# Easy_RFPA_RevB_S2.net
KiCad netlist of a schematic drawn in EAGLE
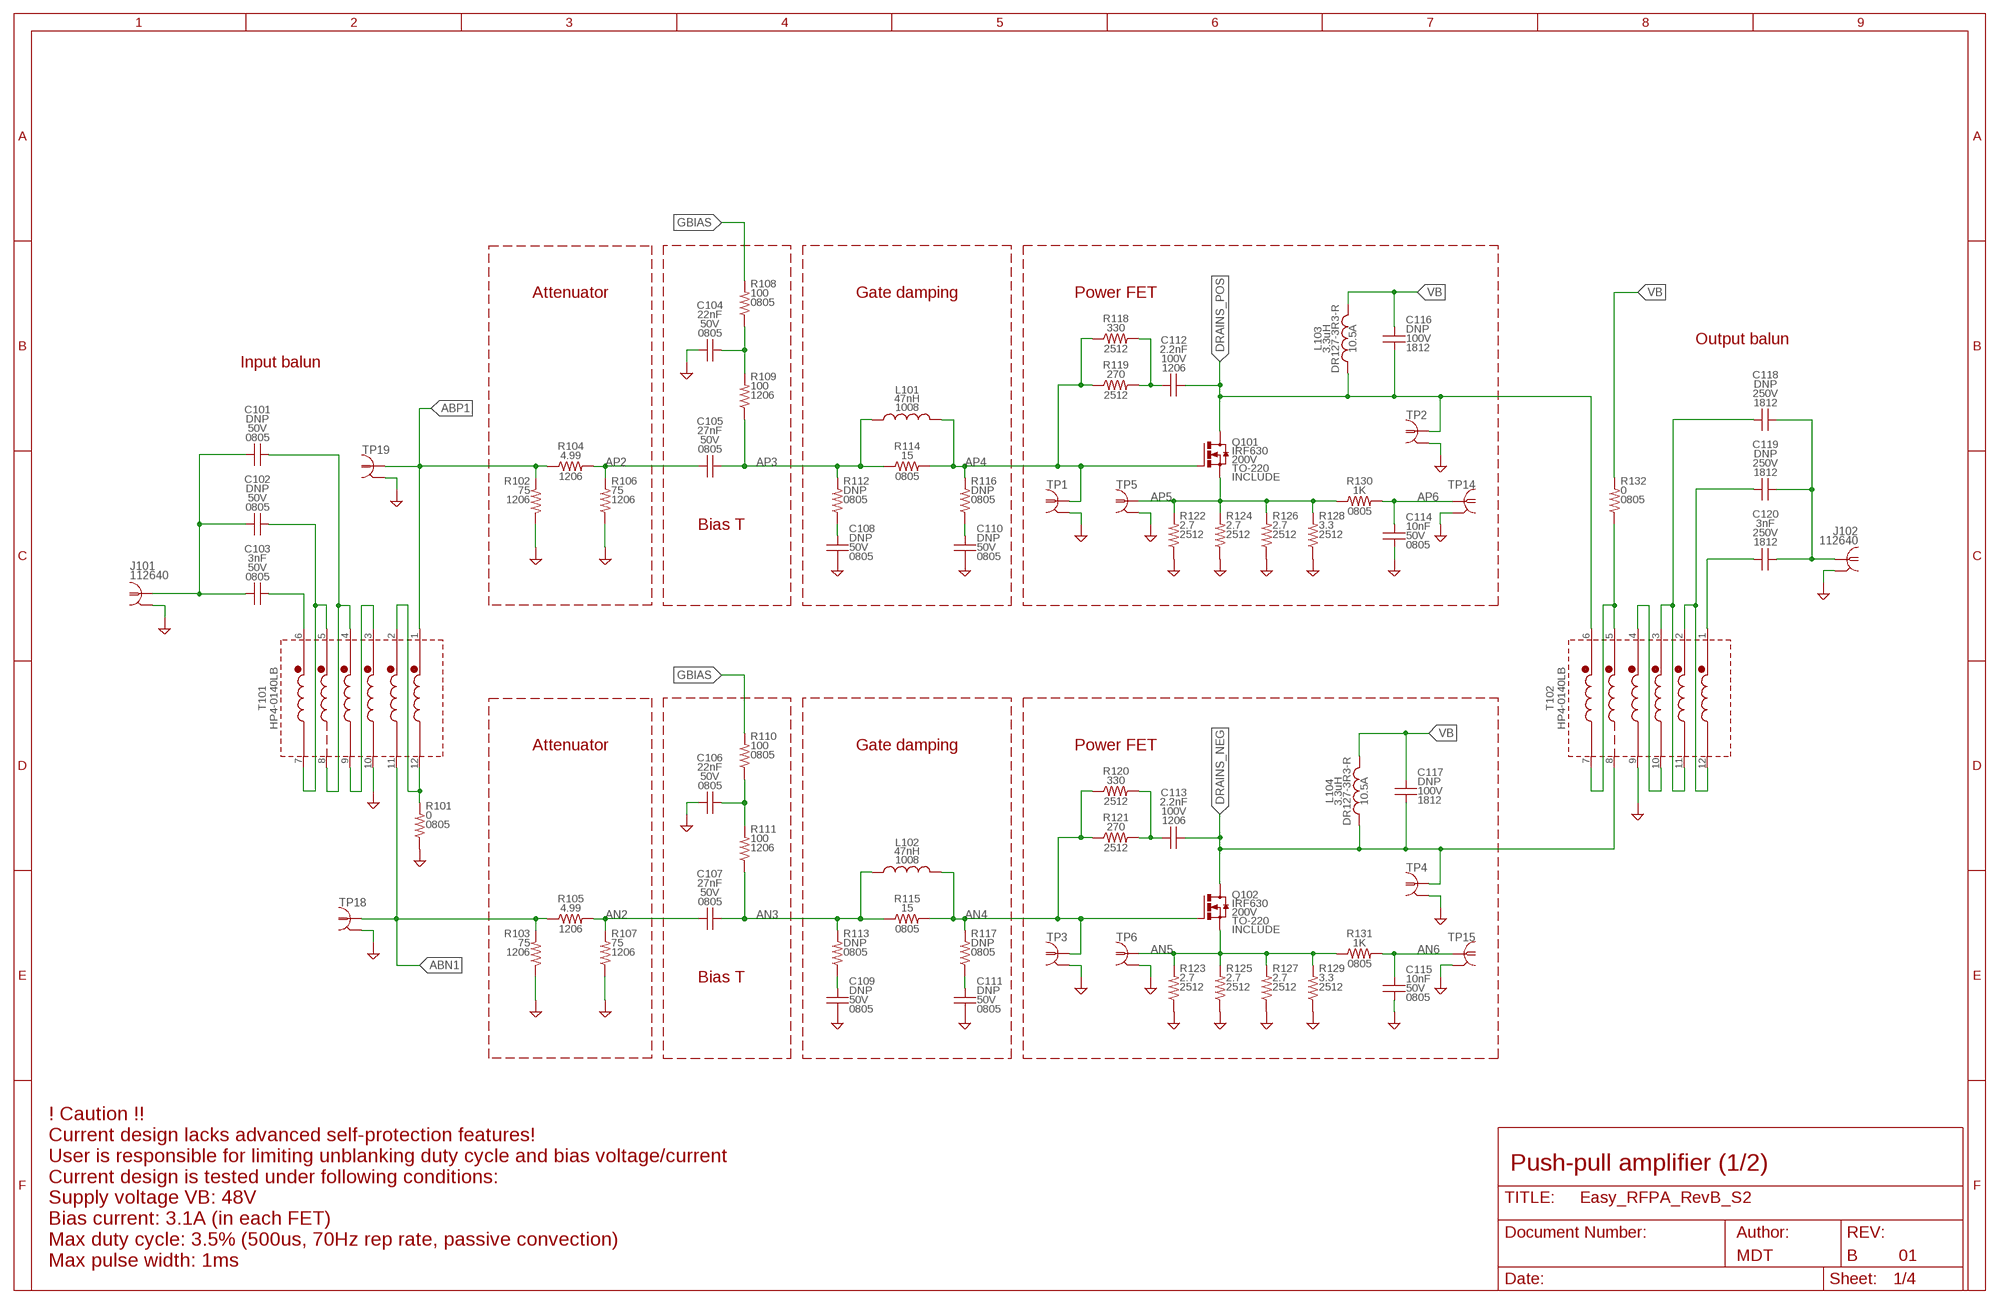
[diagram p0: schematic, sheet 1]
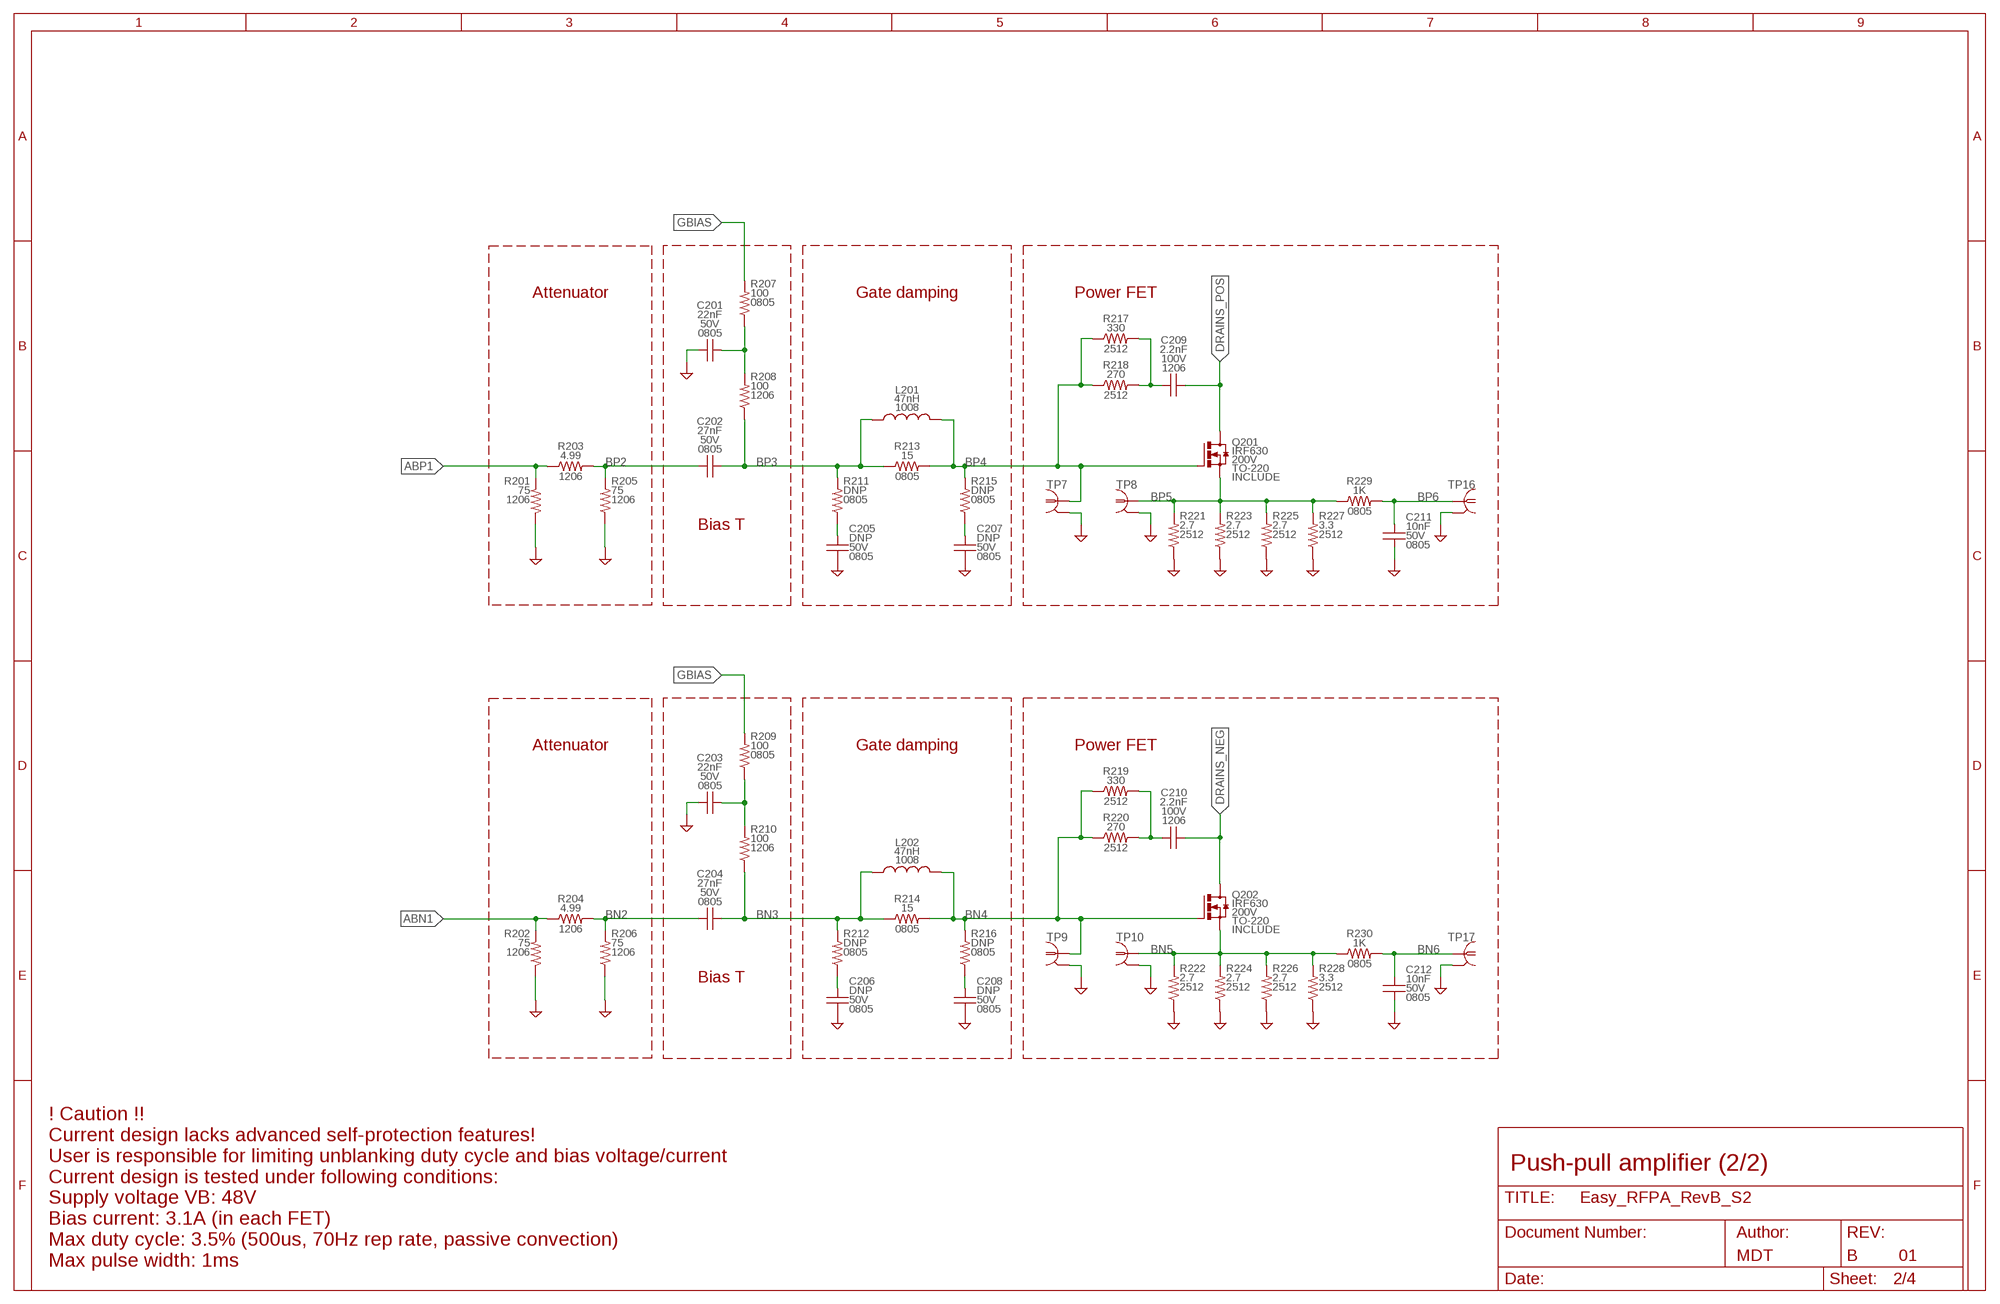
[diagram p1: schematic, sheet 2]
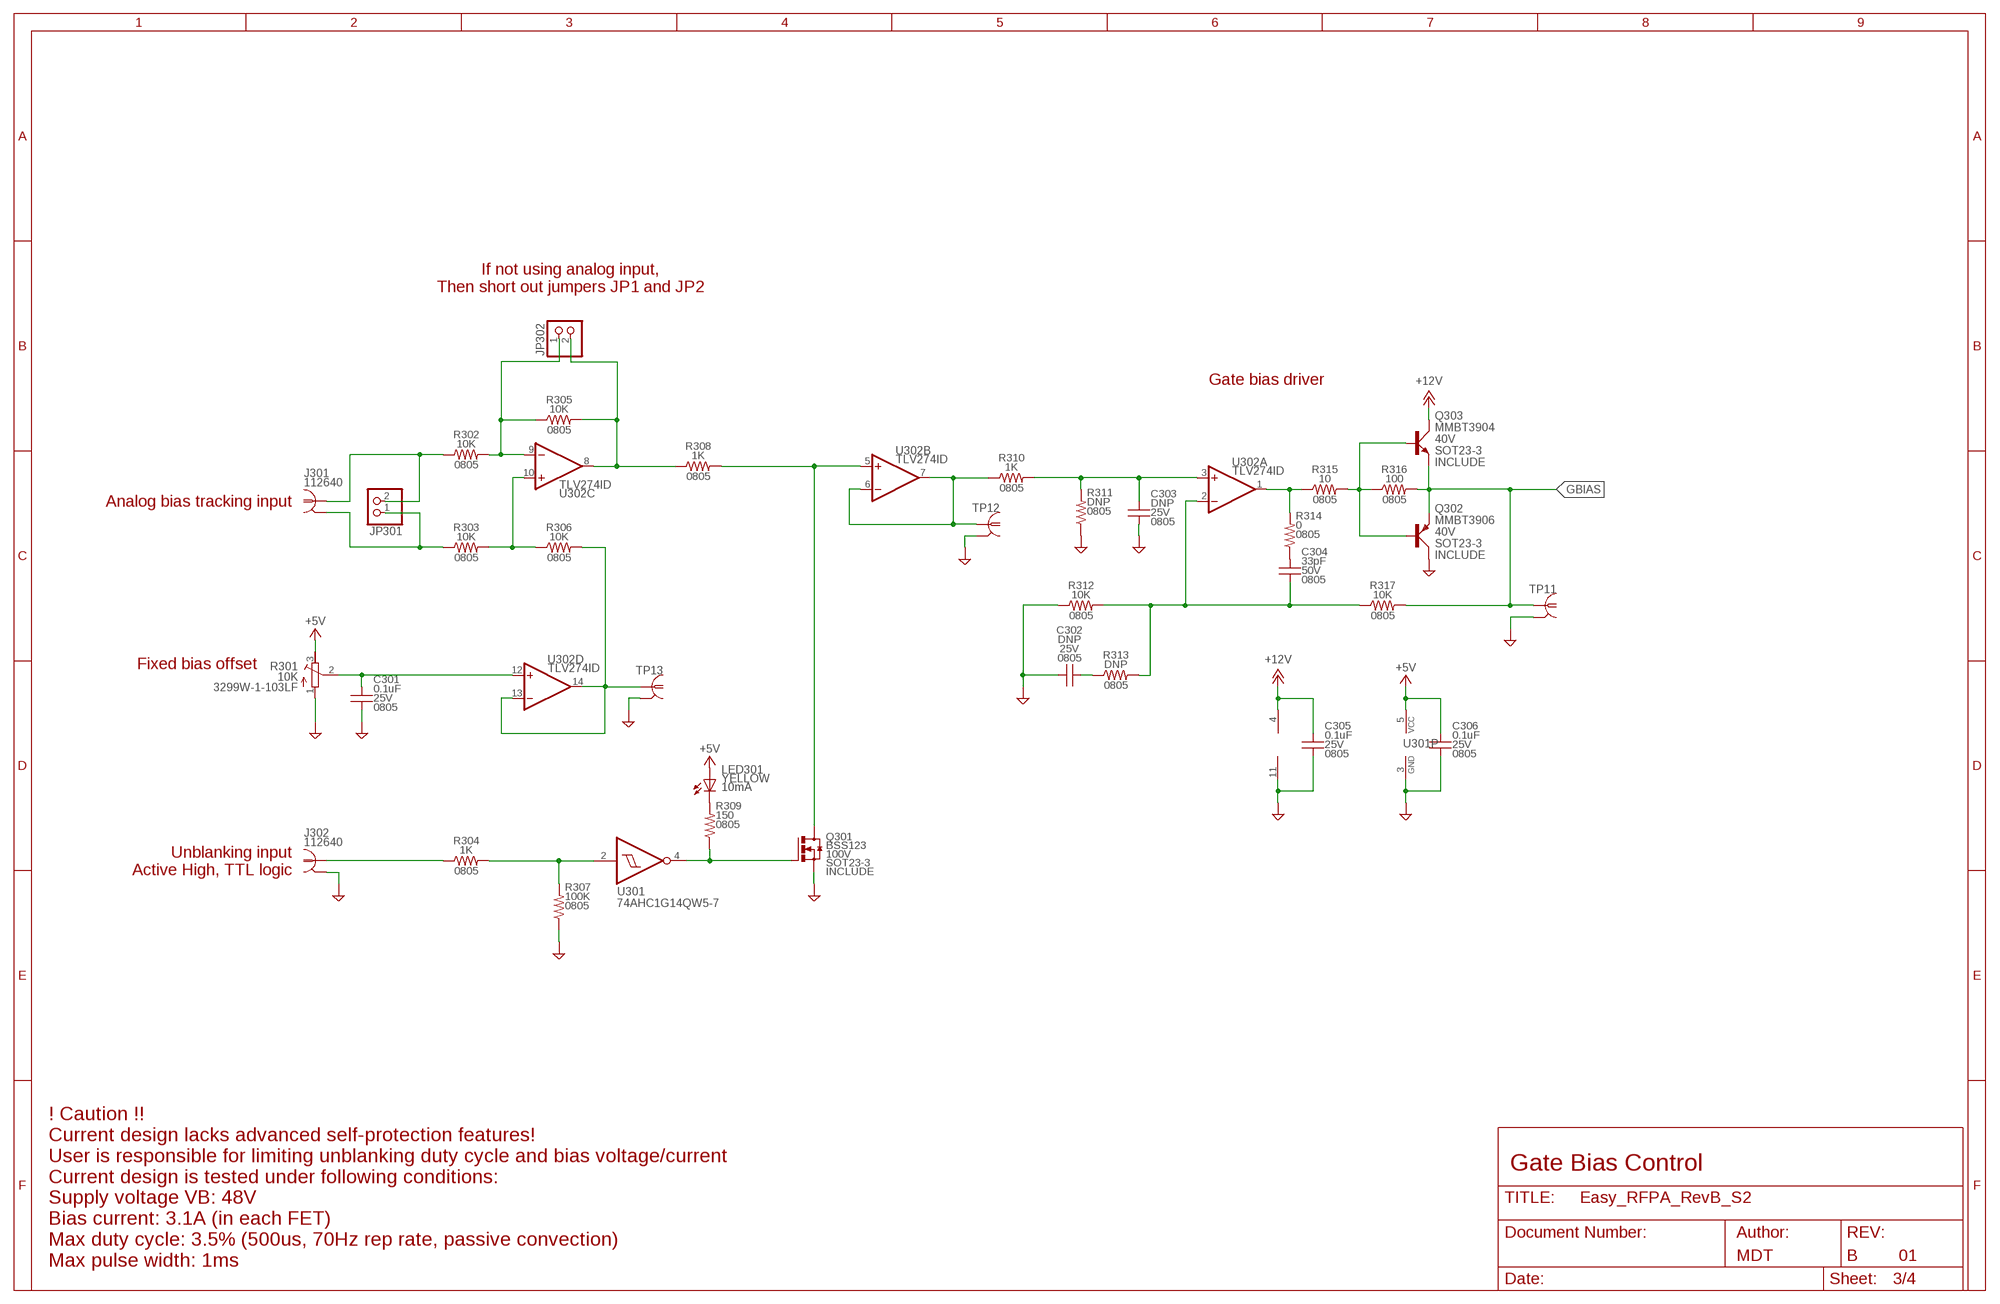
[diagram p2: schematic, sheet 3]
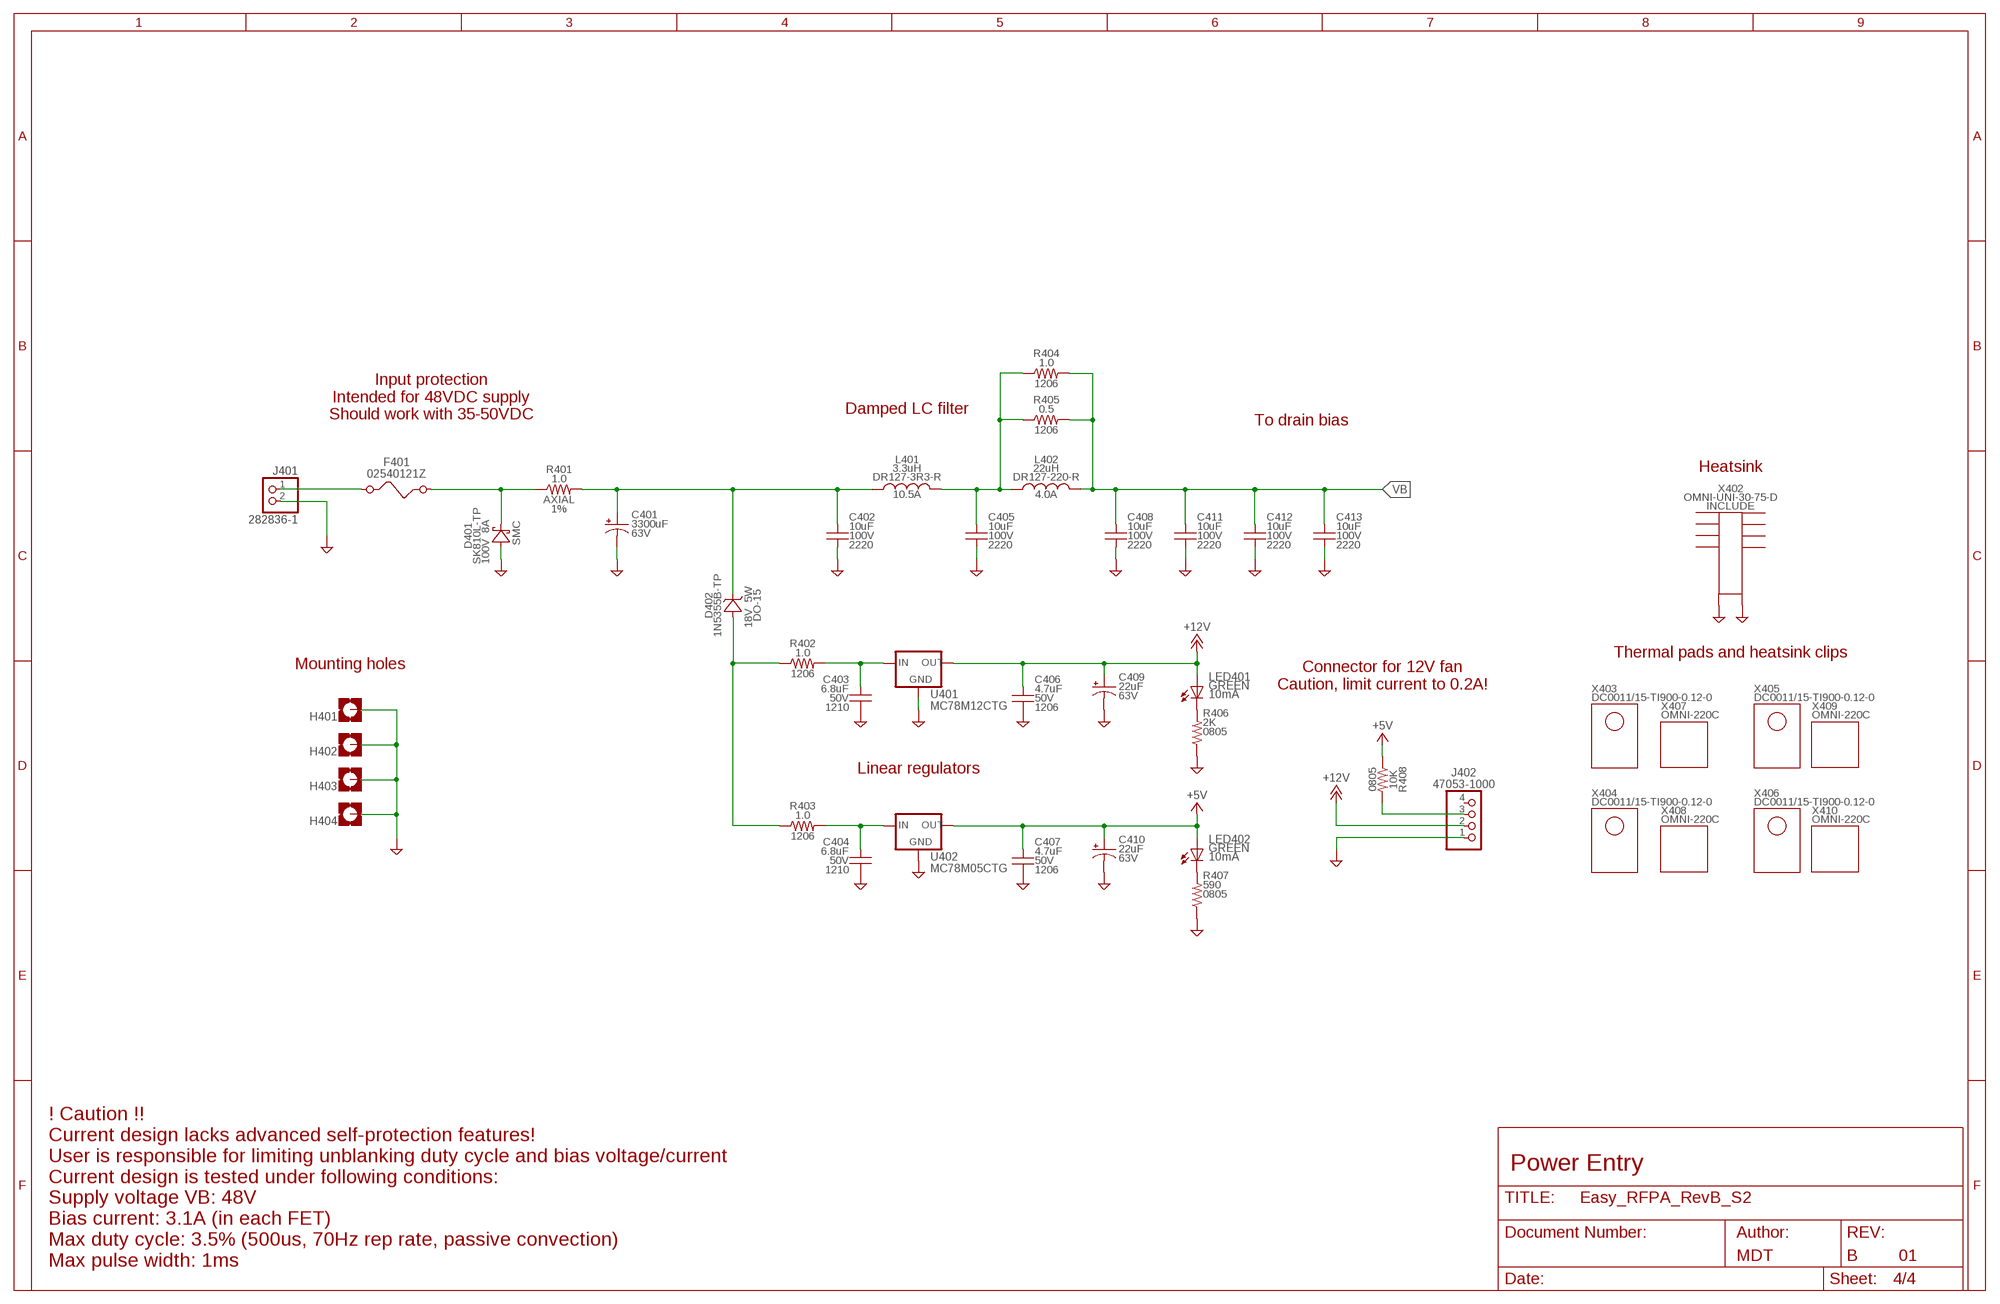
[diagram p3: schematic, sheet 4]

(export (version "E")
  (design (tool "Eeschema 10.0.6"))
  (components
    (comp (ref "C101")
      (value "DNP")
      (footprint "eagle-import:0805_IPC-7351B")
      (fields (field (name "PACKAGE") "0805") (field (name "BOM") "EXCLUDE") (field (name "VOLTAGE") "50V"))
      (libsource (lib "eagle-import") (part "C0805_IPCGEN"))
    )
    (comp (ref "C102")
      (value "DNP")
      (footprint "eagle-import:0805_IPC-7351B")
      (fields (field (name "PACKAGE") "0805") (field (name "BOM") "EXCLUDE") (field (name "VOLTAGE") "50V"))
      (libsource (lib "eagle-import") (part "C0805_IPCGEN"))
    )
    (comp (ref "C103")
      (value "3nF")
      (footprint "eagle-import:0805_IPC-7351B")
      (fields (field (name "PACKAGE") "0805") (field (name "VOLTAGE") "50V"))
      (libsource (lib "eagle-import") (part "C0805_IPCGEN"))
    )
    (comp (ref "C104")
      (value "22nF")
      (footprint "eagle-import:0805_IPC-7351B")
      (fields (field (name "BOM") "INCLUDE") (field (name "PACKAGE") "0805") (field (name "VOLTAGE") "50V"))
      (libsource (lib "eagle-import") (part "C0805_IPCGEN"))
    )
    (comp (ref "C105")
      (value "27nF")
      (footprint "eagle-import:0805_IPC-7351B")
      (fields (field (name "PACKAGE") "0805") (field (name "VOLTAGE") "50V"))
      (libsource (lib "eagle-import") (part "C0805_IPCGEN"))
    )
    (comp (ref "C106")
      (value "22nF")
      (footprint "eagle-import:0805_IPC-7351B")
      (fields (field (name "PACKAGE") "0805") (field (name "VOLTAGE") "50V"))
      (libsource (lib "eagle-import") (part "C0805_IPCGEN"))
    )
    (comp (ref "C107")
      (value "27nF")
      (footprint "eagle-import:0805_IPC-7351B")
      (fields (field (name "PACKAGE") "0805") (field (name "VOLTAGE") "50V"))
      (libsource (lib "eagle-import") (part "C0805_IPCGEN"))
    )
    (comp (ref "C108")
      (value "DNP")
      (footprint "eagle-import:0805_IPC-7351B")
      (fields (field (name "BOM") "EXCLUDE") (field (name "VOLTAGE") "50V"))
      (libsource (lib "eagle-import") (part "C0805_IPCGEN"))
    )
    (comp (ref "C109")
      (value "DNP")
      (footprint "eagle-import:0805_IPC-7351B")
      (fields (field (name "BOM") "EXCLUDE") (field (name "VOLTAGE") "50V"))
      (libsource (lib "eagle-import") (part "C0805_IPCGEN"))
    )
    (comp (ref "C110")
      (value "DNP")
      (footprint "eagle-import:0805_IPC-7351B")
      (fields (field (name "BOM") "EXCLUDE") (field (name "VOLTAGE") "50V"))
      (libsource (lib "eagle-import") (part "C0805_IPCGEN"))
    )
    (comp (ref "C111")
      (value "DNP")
      (footprint "eagle-import:0805_IPC-7351B")
      (fields (field (name "BOM") "EXCLUDE") (field (name "VOLTAGE") "50V"))
      (libsource (lib "eagle-import") (part "C0805_IPCGEN"))
    )
    (comp (ref "C112")
      (value "2.2nF")
      (footprint "eagle-import:C1206")
      (fields (field (name "PACKAGE") "1206") (field (name "VOLTAGE") "100V"))
      (libsource (lib "eagle-import") (part "CC1206GEN"))
    )
    (comp (ref "C113")
      (value "2.2nF")
      (footprint "eagle-import:C1206")
      (fields (field (name "PACKAGE") "1206") (field (name "VOLTAGE") "100V"))
      (libsource (lib "eagle-import") (part "CC1206GEN"))
    )
    (comp (ref "C114")
      (value "10nF")
      (footprint "eagle-import:0805_IPC-7351B")
      (fields (field (name "VOLTAGE") "50V"))
      (libsource (lib "eagle-import") (part "C0805_IPCGEN"))
    )
    (comp (ref "C115")
      (value "10nF")
      (footprint "eagle-import:0805_IPC-7351B")
      (fields (field (name "VOLTAGE") "50V"))
      (libsource (lib "eagle-import") (part "C0805_IPCGEN"))
    )
    (comp (ref "C116")
      (value "DNP")
      (footprint "eagle-import:C1812")
      (fields (field (name "BOM") "EXCLUDE") (field (name "VOLTAGE") "100V"))
      (libsource (lib "eagle-import") (part "CC1812GEN"))
    )
    (comp (ref "C117")
      (value "DNP")
      (footprint "eagle-import:C1812")
      (fields (field (name "BOM") "EXCLUDE") (field (name "VOLTAGE") "100V"))
      (libsource (lib "eagle-import") (part "CC1812GEN"))
    )
    (comp (ref "C118")
      (value "DNP")
      (footprint "eagle-import:C1812")
      (fields (field (name "PACKAGE") "1812") (field (name "BOM") "EXCLUDE") (field (name "VOLTAGE") "250V"))
      (libsource (lib "eagle-import") (part "CC1812GEN"))
    )
    (comp (ref "C119")
      (value "DNP")
      (footprint "eagle-import:C1812")
      (fields (field (name "PACKAGE") "1812") (field (name "BOM") "EXCLUDE") (field (name "VOLTAGE") "250V"))
      (libsource (lib "eagle-import") (part "CC1812GEN"))
    )
    (comp (ref "C120")
      (value "3nF")
      (footprint "eagle-import:C1812")
      (fields (field (name "PACKAGE") "1812") (field (name "VOLTAGE") "250V"))
      (libsource (lib "eagle-import") (part "CC1812GEN"))
    )
    (comp (ref "J101")
      (value "COAX112640BNC_EDGE")
      (footprint "eagle-import:BNC_EDGE")
      (fields (field (name "PARTNO") "112640"))
      (libsource (lib "eagle-import") (part "COAXBNC_EDGE112640"))
    )
    (comp (ref "J102")
      (value "COAX112640BNC_EDGE")
      (footprint "eagle-import:BNC_EDGE")
      (fields (field (name "PARTNO") "112640"))
      (libsource (lib "eagle-import") (part "COAXBNC_EDGE112640"))
    )
    (comp (ref "L101")
      (value "47nH")
      (footprint "eagle-import:L1008")
      (fields (field (name "PARTNO") "1008CS-470XJLC"))
      (libsource (lib "eagle-import") (part "L_CHIP1008L-47N-AIR-5%-1008-1A"))
    )
    (comp (ref "L102")
      (value "47nH")
      (footprint "eagle-import:L1008")
      (fields (field (name "PARTNO") "1008CS-470XJLC"))
      (libsource (lib "eagle-import") (part "L_CHIP1008L-47N-AIR-5%-1008-1A"))
    )
    (comp (ref "L103")
      (value "3.3uH")
      (footprint "eagle-import:DR127")
      (fields (field (name "PARTNO") "DR127-3R3-R"))
      (libsource (lib "eagle-import") (part "LL-3.3U-FERRITE-20%-12.5X12.5MM-10.5A"))
    )
    (comp (ref "L104")
      (value "3.3uH")
      (footprint "eagle-import:DR127")
      (fields (field (name "PARTNO") "DR127-3R3-R"))
      (libsource (lib "eagle-import") (part "LL-3.3U-FERRITE-20%-12.5X12.5MM-10.5A"))
    )
    (comp (ref "Q101")
      (value "IRF520N")
      (footprint "eagle-import:TO220BV")
      (fields (field (name "PARTNO") "IRF630") (field (name "VOLTAGE") "200V"))
      (libsource (lib "eagle-import") (part "MOSFET_NTO-220-VERTIRF630"))
    )
    (comp (ref "Q102")
      (value "IRF630")
      (footprint "eagle-import:TO220BV")
      (fields (field (name "VOLTAGE") "200V"))
      (libsource (lib "eagle-import") (part "MOSFET_NTO-220-VERTIRF630"))
    )
    (comp (ref "R101")
      (value "0")
      (footprint "eagle-import:0805_IPC-7351B")
      (libsource (lib "eagle-import") (part "R0805_IPCGEN"))
    )
    (comp (ref "R102")
      (value "75")
      (footprint "eagle-import:1206_IPC-7351B")
      (libsource (lib "eagle-import") (part "R1206_IPCGEN"))
    )
    (comp (ref "R103")
      (value "75")
      (footprint "eagle-import:1206_IPC-7351B")
      (libsource (lib "eagle-import") (part "R1206_IPCGEN"))
    )
    (comp (ref "R104")
      (value "4.99")
      (footprint "eagle-import:1206_IPC-7351B")
      (libsource (lib "eagle-import") (part "R901206_IPCGEN"))
    )
    (comp (ref "R105")
      (value "4.99")
      (footprint "eagle-import:1206_IPC-7351B")
      (libsource (lib "eagle-import") (part "R901206_IPCGEN"))
    )
    (comp (ref "R106")
      (value "75")
      (footprint "eagle-import:1206_IPC-7351B")
      (libsource (lib "eagle-import") (part "R1206_IPCGEN"))
    )
    (comp (ref "R107")
      (value "75")
      (footprint "eagle-import:1206_IPC-7351B")
      (libsource (lib "eagle-import") (part "R1206_IPCGEN"))
    )
    (comp (ref "R108")
      (value "100")
      (footprint "eagle-import:0805_IPC-7351B")
      (libsource (lib "eagle-import") (part "R0805_IPCGEN"))
    )
    (comp (ref "R109")
      (value "100")
      (footprint "eagle-import:1206_IPC-7351B")
      (libsource (lib "eagle-import") (part "R1206_IPCGEN"))
    )
    (comp (ref "R110")
      (value "100")
      (footprint "eagle-import:0805_IPC-7351B")
      (libsource (lib "eagle-import") (part "R0805_IPCGEN"))
    )
    (comp (ref "R111")
      (value "100")
      (footprint "eagle-import:1206_IPC-7351B")
      (libsource (lib "eagle-import") (part "R1206_IPCGEN"))
    )
    (comp (ref "R112")
      (value "DNP")
      (footprint "eagle-import:0805_IPC-7351B")
      (fields (field (name "BOM") "EXCLUDE"))
      (libsource (lib "eagle-import") (part "R0805_IPCGEN"))
    )
    (comp (ref "R113")
      (value "DNP")
      (footprint "eagle-import:0805_IPC-7351B")
      (fields (field (name "BOM") "EXCLUDE"))
      (libsource (lib "eagle-import") (part "R0805_IPCGEN"))
    )
    (comp (ref "R114")
      (value "15")
      (footprint "eagle-import:0805_IPC-7351B")
      (libsource (lib "eagle-import") (part "R900805_IPCGEN"))
    )
    (comp (ref "R115")
      (value "15")
      (footprint "eagle-import:0805_IPC-7351B")
      (libsource (lib "eagle-import") (part "R900805_IPCGEN"))
    )
    (comp (ref "R116")
      (value "DNP")
      (footprint "eagle-import:0805_IPC-7351B")
      (fields (field (name "BOM") "EXCLUDE"))
      (libsource (lib "eagle-import") (part "R0805_IPCGEN"))
    )
    (comp (ref "R117")
      (value "DNP")
      (footprint "eagle-import:0805_IPC-7351B")
      (fields (field (name "BOM") "EXCLUDE"))
      (libsource (lib "eagle-import") (part "R0805_IPCGEN"))
    )
    (comp (ref "R118")
      (value "330")
      (footprint "eagle-import:R2512")
      (libsource (lib "eagle-import") (part "R90R2512GEN"))
    )
    (comp (ref "R119")
      (value "270")
      (footprint "eagle-import:R2512")
      (libsource (lib "eagle-import") (part "R90R2512GEN"))
    )
    (comp (ref "R120")
      (value "330")
      (footprint "eagle-import:R2512")
      (libsource (lib "eagle-import") (part "R90R2512GEN"))
    )
    (comp (ref "R121")
      (value "270")
      (footprint "eagle-import:R2512")
      (libsource (lib "eagle-import") (part "R90R2512GEN"))
    )
    (comp (ref "R122")
      (value "2.7")
      (footprint "eagle-import:R2512")
      (libsource (lib "eagle-import") (part "RR2512GEN"))
    )
    (comp (ref "R123")
      (value "2.7")
      (footprint "eagle-import:R2512")
      (libsource (lib "eagle-import") (part "RR2512GEN"))
    )
    (comp (ref "R124")
      (value "2.7")
      (footprint "eagle-import:R2512")
      (libsource (lib "eagle-import") (part "RR2512GEN"))
    )
    (comp (ref "R125")
      (value "2.7")
      (footprint "eagle-import:R2512")
      (libsource (lib "eagle-import") (part "RR2512GEN"))
    )
    (comp (ref "R126")
      (value "2.7")
      (footprint "eagle-import:R2512")
      (libsource (lib "eagle-import") (part "RR2512GEN"))
    )
    (comp (ref "R127")
      (value "2.7")
      (footprint "eagle-import:R2512")
      (libsource (lib "eagle-import") (part "RR2512GEN"))
    )
    (comp (ref "R128")
      (value "3.3")
      (footprint "eagle-import:R2512")
      (libsource (lib "eagle-import") (part "RR2512GEN"))
    )
    (comp (ref "R129")
      (value "3.3")
      (footprint "eagle-import:R2512")
      (libsource (lib "eagle-import") (part "RR2512GEN"))
    )
    (comp (ref "R130")
      (value "1K")
      (footprint "eagle-import:0805_IPC-7351B")
      (libsource (lib "eagle-import") (part "R900805_IPCGEN"))
    )
    (comp (ref "R131")
      (value "1K")
      (footprint "eagle-import:0805_IPC-7351B")
      (libsource (lib "eagle-import") (part "R900805_IPCGEN"))
    )
    (comp (ref "R132")
      (value "0")
      (footprint "eagle-import:0805_IPC-7351B")
      (libsource (lib "eagle-import") (part "R0805_IPCGEN"))
    )
    (comp (ref "T101")
      (value "HP4_TRAFO")
      (footprint "eagle-import:HP4")
      (fields (field (name "PARTNO") "HP4-0140LB"))
      (libsource (lib "eagle-import") (part "HP4_TRAFO"))
    )
    (comp (ref "T102")
      (value "HP4_TRAFO")
      (footprint "eagle-import:HP4")
      (fields (field (name "PARTNO") "HP4-0140LB"))
      (libsource (lib "eagle-import") (part "HP4_TRAFO"))
    )
    (comp (ref "TP1")
      (value "PROBE_TPTP_5MM")
      (footprint "eagle-import:PROBE_TP_5MM")
      (libsource (lib "eagle-import") (part "PROBE_TPTP_5MM"))
    )
    (comp (ref "TP2")
      (value "PROBE_TPTP_7P5MM")
      (footprint "eagle-import:PROBE_TP_7P5MM")
      (libsource (lib "eagle-import") (part "PROBE_TPTP_7P5MM"))
    )
    (comp (ref "TP3")
      (value "PROBE_TPTP_5MM")
      (footprint "eagle-import:PROBE_TP_5MM")
      (libsource (lib "eagle-import") (part "PROBE_TPTP_5MM"))
    )
    (comp (ref "TP4")
      (value "PROBE_TPTP_7P5MM")
      (footprint "eagle-import:PROBE_TP_7P5MM")
      (libsource (lib "eagle-import") (part "PROBE_TPTP_7P5MM"))
    )
    (comp (ref "TP5")
      (value "PROBE_TPTP_7P5MM")
      (footprint "eagle-import:PROBE_TP_7P5MM")
      (libsource (lib "eagle-import") (part "PROBE_TPTP_7P5MM"))
    )
    (comp (ref "TP6")
      (value "PROBE_TPTP_7P5MM")
      (footprint "eagle-import:PROBE_TP_7P5MM")
      (libsource (lib "eagle-import") (part "PROBE_TPTP_7P5MM"))
    )
    (comp (ref "TP14")
      (value "PROBE_TPTP_5MM")
      (footprint "eagle-import:PROBE_TP_5MM")
      (libsource (lib "eagle-import") (part "PROBE_TPTP_5MM"))
    )
    (comp (ref "TP15")
      (value "PROBE_TPTP_5MM")
      (footprint "eagle-import:PROBE_TP_5MM")
      (libsource (lib "eagle-import") (part "PROBE_TPTP_5MM"))
    )
    (comp (ref "TP18")
      (value "PROBE_TPTP_5MM")
      (footprint "eagle-import:PROBE_TP_5MM")
      (libsource (lib "eagle-import") (part "PROBE_TPTP_5MM"))
    )
    (comp (ref "TP19")
      (value "PROBE_TPTP_5MM")
      (footprint "eagle-import:PROBE_TP_5MM")
      (libsource (lib "eagle-import") (part "PROBE_TPTP_5MM"))
    )
    (comp (ref "C401")
      (value "3300uF")
      (footprint "eagle-import:EB25D")
      (fields (field (name "PARTNO") "MAL225638332E3") (field (name "VOLTAGE") "63V"))
      (libsource (lib "eagle-import") (part "CPOLEB25DC-3300U-63V-20%-25DX37L-ELEC"))
    )
    (comp (ref "C402")
      (value "10uF")
      (footprint "eagle-import:C2220_CKG57N")
      (fields
        (field (name "BOM") "INCLUDE")
        (field (name "PACKAGE") "2220")
        (field (name "PARTNO") "CGA9N3X7S2A106M230KE")
        (field (name "VOLTAGE") "100V")
      )
      (libsource (lib "eagle-import") (part "CC2220_CKG57NCC-10U-100V-20%-2220-X7T"))
    )
    (comp (ref "C403")
      (value "6.8uF")
      (footprint "eagle-import:C1210")
      (fields (field (name "DIALECTRIC") "X7S") (field (name "VOLTAGE") "50V"))
      (libsource (lib "eagle-import") (part "CC1210GEN"))
    )
    (comp (ref "C404")
      (value "6.8uF")
      (footprint "eagle-import:C1210")
      (fields (field (name "DIALECTRIC") "X7S") (field (name "VOLTAGE") "50V"))
      (libsource (lib "eagle-import") (part "CC1210GEN"))
    )
    (comp (ref "C405")
      (value "10uF")
      (footprint "eagle-import:C2220_CKG57N")
      (fields
        (field (name "BOM") "INCLUDE")
        (field (name "PACKAGE") "2220")
        (field (name "PARTNO") "CGA9N3X7S2A106M230KE")
        (field (name "VOLTAGE") "100V")
      )
      (libsource (lib "eagle-import") (part "CC2220_CKG57NCC-10U-100V-20%-2220-X7T"))
    )
    (comp (ref "C406")
      (value "4.7uF")
      (footprint "eagle-import:C1206")
      (fields (field (name "DIALECTRIC") "X7R") (field (name "VOLTAGE") "50V"))
      (libsource (lib "eagle-import") (part "CC1206GEN"))
    )
    (comp (ref "C407")
      (value "4.7uF")
      (footprint "eagle-import:C1206")
      (fields (field (name "DIALECTRIC") "X7R") (field (name "VOLTAGE") "50V"))
      (libsource (lib "eagle-import") (part "CC1206GEN"))
    )
    (comp (ref "C408")
      (value "10uF")
      (footprint "eagle-import:C2220_CKG57N")
      (fields (field (name "PARTNO") "CGA9N3X7S2A106M230KE") (field (name "VOLTAGE") "100V"))
      (libsource (lib "eagle-import") (part "CC2220_CKG57NCC-10U-100V-20%-2220-X7T"))
    )
    (comp (ref "C409")
      (value "22uF")
      (footprint "eagle-import:E2,5-7")
      (fields (field (name "PARTNO") "860010773010") (field (name "VOLTAGE") "63V"))
      (libsource (lib "eagle-import") (part "CPOLE2,5-7C-22U-63V-20%-6.3DX12.5L-ELEC"))
    )
    (comp (ref "C410")
      (value "22uF")
      (footprint "eagle-import:E2,5-7")
      (fields (field (name "PARTNO") "860010773010") (field (name "VOLTAGE") "63V"))
      (libsource (lib "eagle-import") (part "CPOLE2,5-7C-22U-63V-20%-6.3DX12.5L-ELEC"))
    )
    (comp (ref "C411")
      (value "10uF")
      (footprint "eagle-import:C2220_CKG57N")
      (fields (field (name "PARTNO") "CGA9N3X7S2A106M230KE") (field (name "VOLTAGE") "100V"))
      (libsource (lib "eagle-import") (part "CC2220_CKG57NCC-10U-100V-20%-2220-X7T"))
    )
    (comp (ref "C412")
      (value "10uF")
      (footprint "eagle-import:C2220_CKG57N")
      (fields (field (name "PARTNO") "CGA9N3X7S2A106M230KE") (field (name "VOLTAGE") "100V"))
      (libsource (lib "eagle-import") (part "CC2220_CKG57NCC-10U-100V-20%-2220-X7T"))
    )
    (comp (ref "C413")
      (value "10uF")
      (footprint "eagle-import:C2220_CKG57N")
      (fields (field (name "PARTNO") "CGA9N3X7S2A106M230KE") (field (name "VOLTAGE") "100V"))
      (libsource (lib "eagle-import") (part "CC2220_CKG57NCC-10U-100V-20%-2220-X7T"))
    )
    (comp (ref "D401")
      (value "D-SCHOTTKYSK810L-TPSMC")
      (footprint "eagle-import:DO-214AB(SMC)")
      (fields (field (name "PARTNO") "SK810L-TP") (field (name "VOLTAGE") "100V"))
      (libsource (lib "eagle-import") (part "D-SCHOTTKYSMCSK810L-TP"))
    )
    (comp (ref "D402")
      (value "D-ZENER1N5355B-TPDO15-12")
      (footprint "eagle-import:DO15-12")
      (fields (field (name "PARTNO") "1N5355B-TP") (field (name "POWER") "5W") (field (name "VOLTAGE") "18V"))
      (libsource (lib "eagle-import") (part "D-ZENERDO15-121N5355B-TP"))
    )
    (comp (ref "F401")
      (value "FUSE_2P")
      (footprint "eagle-import:02540121Z")
      (fields (field (name "PARTNO") "02540121Z"))
      (libsource (lib "eagle-import") (part "FUSE_2P"))
    )
    (comp (ref "H401")
      (value "MOUNT-PAD-SQUARE3.2")
      (footprint "eagle-import:3,2-PAD-SQUARE")
      (libsource (lib "eagle-import") (part "MOUNT-PAD-SQUARE3.2"))
    )
    (comp (ref "H402")
      (value "MOUNT-PAD-SQUARE3.2")
      (footprint "eagle-import:3,2-PAD-SQUARE")
      (libsource (lib "eagle-import") (part "MOUNT-PAD-SQUARE3.2"))
    )
    (comp (ref "H403")
      (value "MOUNT-PAD-SQUARE3.2")
      (footprint "eagle-import:3,2-PAD-SQUARE")
      (libsource (lib "eagle-import") (part "MOUNT-PAD-SQUARE3.2"))
    )
    (comp (ref "H404")
      (value "MOUNT-PAD-SQUARE3.2")
      (footprint "eagle-import:3,2-PAD-SQUARE")
      (libsource (lib "eagle-import") (part "MOUNT-PAD-SQUARE3.2"))
    )
    (comp (ref "J401")
      (value "HDR_2X1282836-1282836-1")
      (footprint "eagle-import:W237-02")
      (fields (field (name "PARTNO") "282836-1"))
      (libsource (lib "eagle-import") (part "HDR_2X1282836-1282836-1"))
    )
    (comp (ref "J402")
      (value "KK_PCFAN")
      (footprint "eagle-import:47053-1000")
      (fields (field (name "PARTNO") "47053-1000"))
      (libsource (lib "eagle-import") (part "KK_PCFAN"))
    )
    (comp (ref "L401")
      (value "3.3uH")
      (footprint "eagle-import:DR127")
      (fields (field (name "PARTNO") "DR127-3R3-R"))
      (libsource (lib "eagle-import") (part "LL-3.3U-FERRITE-20%-12.5X12.5MM-10.5A"))
    )
    (comp (ref "L402")
      (value "22uH")
      (footprint "eagle-import:DR127")
      (fields (field (name "PARTNO") "DR127-220-R"))
      (libsource (lib "eagle-import") (part "LL-22U-FERRITE-20%-12.5X12.5MM-4A"))
    )
    (comp (ref "LED401")
      (value "LEDHLMP-3962-F0002T1_3/4")
      (footprint "eagle-import:LED5MM")
      (fields (field (name "PARTNO") "HLMP-3962-F0002"))
      (libsource (lib "eagle-import") (part "LEDT1_3/4HLMP-3962-F0002"))
    )
    (comp (ref "LED402")
      (value "LEDHLMP-3962-F0002T1_3/4")
      (footprint "eagle-import:LED5MM")
      (fields (field (name "PARTNO") "HLMP-3962-F0002"))
      (libsource (lib "eagle-import") (part "LEDT1_3/4HLMP-3962-F0002"))
    )
    (comp (ref "R401")
      (value "1.0")
      (footprint "eagle-import:P0817V")
      (fields (field (name "PARTNO") "PAC300001008FAC000") (field (name "POWER") "3W"))
      (libsource (lib "eagle-import") (part "R90P0817VR-1.0-1%-AXIAL-3W"))
    )
    (comp (ref "R402")
      (value "1.0")
      (footprint "eagle-import:R1206")
      (libsource (lib "eagle-import") (part "R90R1206GEN"))
    )
    (comp (ref "R403")
      (value "1.0")
      (footprint "eagle-import:R1206")
      (libsource (lib "eagle-import") (part "R90R1206GEN"))
    )
    (comp (ref "R404")
      (value "1.0")
      (footprint "eagle-import:1206_IPC-7351B")
      (libsource (lib "eagle-import") (part "R901206_IPCGEN"))
    )
    (comp (ref "R405")
      (value "0.5")
      (footprint "eagle-import:1206_IPC-7351B")
      (libsource (lib "eagle-import") (part "R901206_IPCGEN"))
    )
    (comp (ref "R406")
      (value "2K")
      (footprint "eagle-import:0805_IPC-7351B")
      (libsource (lib "eagle-import") (part "R0805_IPCGEN"))
    )
    (comp (ref "R407")
      (value "590")
      (footprint "eagle-import:0805_IPC-7351B")
      (libsource (lib "eagle-import") (part "R0805_IPCGEN"))
    )
    (comp (ref "R408")
      (value "10K")
      (footprint "eagle-import:0805_IPC-7351B")
      (libsource (lib "eagle-import") (part "R900805_IPCGEN"))
    )
    (comp (ref "U401")
      (value "LDO_3TERMMC78M12CTGTO220_VERT")
      (footprint "eagle-import:TO220BV")
      (fields (field (name "PARTNO") "MC78M12CTG"))
      (libsource (lib "eagle-import") (part "LDO_3TERMTO220_VERTMC78M12CTG"))
    )
    (comp (ref "U402")
      (value "LDO_3TERMMC78M05CTGTO220_VERT")
      (footprint "eagle-import:TO220BV")
      (fields (field (name "PARTNO") "MC78M05CTG"))
      (libsource (lib "eagle-import") (part "LDO_3TERMTO220_VERTMC78M05CTG"))
    )
    (comp (ref "X402")
      (value "HEATSINK_OMNI_DUALOMNI-UNI-30-75-D30-75-D")
      (footprint "eagle-import:OMNI-UNI-30-75-D")
      (fields (field (name "PARTNO") "OMNI-UNI-30-75-D"))
      (libsource (lib "eagle-import") (part "HEATSINK_OMNI_DUAL30-75-DOMNI-UNI-30-75-D"))
    )
    (comp (ref "C201")
      (value "22nF")
      (footprint "eagle-import:0805_IPC-7351B")
      (fields (field (name "PACKAGE") "0805") (field (name "VOLTAGE") "50V"))
      (libsource (lib "eagle-import") (part "C0805_IPCGEN"))
    )
    (comp (ref "C202")
      (value "27nF")
      (footprint "eagle-import:0805_IPC-7351B")
      (fields (field (name "PACKAGE") "0805") (field (name "VOLTAGE") "50V"))
      (libsource (lib "eagle-import") (part "C0805_IPCGEN"))
    )
    (comp (ref "C203")
      (value "22nF")
      (footprint "eagle-import:0805_IPC-7351B")
      (fields (field (name "PACKAGE") "0805") (field (name "VOLTAGE") "50V"))
      (libsource (lib "eagle-import") (part "C0805_IPCGEN"))
    )
    (comp (ref "C204")
      (value "27nF")
      (footprint "eagle-import:0805_IPC-7351B")
      (fields (field (name "PACKAGE") "0805") (field (name "VOLTAGE") "50V"))
      (libsource (lib "eagle-import") (part "C0805_IPCGEN"))
    )
    (comp (ref "C205")
      (value "DNP")
      (footprint "eagle-import:0805_IPC-7351B")
      (fields (field (name "BOM") "EXCLUDE") (field (name "VOLTAGE") "50V"))
      (libsource (lib "eagle-import") (part "C0805_IPCGEN"))
    )
    (comp (ref "C206")
      (value "DNP")
      (footprint "eagle-import:0805_IPC-7351B")
      (fields (field (name "BOM") "EXCLUDE") (field (name "VOLTAGE") "50V"))
      (libsource (lib "eagle-import") (part "C0805_IPCGEN"))
    )
    (comp (ref "C207")
      (value "DNP")
      (footprint "eagle-import:0805_IPC-7351B")
      (fields (field (name "BOM") "EXCLUDE") (field (name "VOLTAGE") "50V"))
      (libsource (lib "eagle-import") (part "C0805_IPCGEN"))
    )
    (comp (ref "C208")
      (value "DNP")
      (footprint "eagle-import:0805_IPC-7351B")
      (fields (field (name "BOM") "EXCLUDE") (field (name "VOLTAGE") "50V"))
      (libsource (lib "eagle-import") (part "C0805_IPCGEN"))
    )
    (comp (ref "C209")
      (value "2.2nF")
      (footprint "eagle-import:C1206")
      (fields (field (name "PACKAGE") "1206") (field (name "VOLTAGE") "100V"))
      (libsource (lib "eagle-import") (part "CC1206GEN"))
    )
    (comp (ref "C210")
      (value "2.2nF")
      (footprint "eagle-import:C1206")
      (fields (field (name "PACKAGE") "1206") (field (name "VOLTAGE") "100V"))
      (libsource (lib "eagle-import") (part "CC1206GEN"))
    )
    (comp (ref "C211")
      (value "10nF")
      (footprint "eagle-import:0805_IPC-7351B")
      (fields (field (name "VOLTAGE") "50V"))
      (libsource (lib "eagle-import") (part "C0805_IPCGEN"))
    )
    (comp (ref "C212")
      (value "10nF")
      (footprint "eagle-import:0805_IPC-7351B")
      (fields (field (name "VOLTAGE") "50V"))
      (libsource (lib "eagle-import") (part "C0805_IPCGEN"))
    )
    (comp (ref "L201")
      (value "47nH")
      (footprint "eagle-import:L1008")
      (fields (field (name "PARTNO") "1008CS-470XJLC"))
      (libsource (lib "eagle-import") (part "L_CHIP1008L-47N-AIR-5%-1008-1A"))
    )
    (comp (ref "L202")
      (value "47nH")
      (footprint "eagle-import:L1008")
      (fields (field (name "PARTNO") "1008CS-470XJLC"))
      (libsource (lib "eagle-import") (part "L_CHIP1008L-47N-AIR-5%-1008-1A"))
    )
    (comp (ref "Q201")
      (value "IRF630")
      (footprint "eagle-import:TO220BV")
      (fields (field (name "VOLTAGE") "200V"))
      (libsource (lib "eagle-import") (part "MOSFET_NTO-220-VERTIRF630"))
    )
    (comp (ref "Q202")
      (value "IRF630")
      (footprint "eagle-import:TO220BV")
      (fields (field (name "VOLTAGE") "200V"))
      (libsource (lib "eagle-import") (part "MOSFET_NTO-220-VERTIRF630"))
    )
    (comp (ref "R201")
      (value "75")
      (footprint "eagle-import:1206_IPC-7351B")
      (libsource (lib "eagle-import") (part "R1206_IPCGEN"))
    )
    (comp (ref "R202")
      (value "75")
      (footprint "eagle-import:1206_IPC-7351B")
      (libsource (lib "eagle-import") (part "R1206_IPCGEN"))
    )
    (comp (ref "R203")
      (value "4.99")
      (footprint "eagle-import:1206_IPC-7351B")
      (libsource (lib "eagle-import") (part "R901206_IPCGEN"))
    )
    (comp (ref "R204")
      (value "4.99")
      (footprint "eagle-import:1206_IPC-7351B")
      (libsource (lib "eagle-import") (part "R901206_IPCGEN"))
    )
    (comp (ref "R205")
      (value "75")
      (footprint "eagle-import:1206_IPC-7351B")
      (libsource (lib "eagle-import") (part "R1206_IPCGEN"))
    )
    (comp (ref "R206")
      (value "75")
      (footprint "eagle-import:1206_IPC-7351B")
      (libsource (lib "eagle-import") (part "R1206_IPCGEN"))
    )
    (comp (ref "R207")
      (value "100")
      (footprint "eagle-import:0805_IPC-7351B")
      (libsource (lib "eagle-import") (part "R0805_IPCGEN"))
    )
    (comp (ref "R208")
      (value "100")
      (footprint "eagle-import:1206_IPC-7351B")
      (libsource (lib "eagle-import") (part "R1206_IPCGEN"))
    )
    (comp (ref "R209")
      (value "100")
      (footprint "eagle-import:0805_IPC-7351B")
      (libsource (lib "eagle-import") (part "R0805_IPCGEN"))
    )
    (comp (ref "R210")
      (value "100")
      (footprint "eagle-import:1206_IPC-7351B")
      (libsource (lib "eagle-import") (part "R1206_IPCGEN"))
    )
    (comp (ref "R211")
      (value "DNP")
      (footprint "eagle-import:0805_IPC-7351B")
      (fields (field (name "BOM") "EXCLUDE"))
      (libsource (lib "eagle-import") (part "R0805_IPCGEN"))
    )
    (comp (ref "R212")
      (value "DNP")
      (footprint "eagle-import:0805_IPC-7351B")
      (fields (field (name "BOM") "EXCLUDE"))
      (libsource (lib "eagle-import") (part "R0805_IPCGEN"))
    )
    (comp (ref "R213")
      (value "15")
      (footprint "eagle-import:0805_IPC-7351B")
      (libsource (lib "eagle-import") (part "R900805_IPCGEN"))
    )
    (comp (ref "R214")
      (value "15")
      (footprint "eagle-import:0805_IPC-7351B")
      (libsource (lib "eagle-import") (part "R900805_IPCGEN"))
    )
    (comp (ref "R215")
      (value "DNP")
      (footprint "eagle-import:0805_IPC-7351B")
      (fields (field (name "BOM") "EXCLUDE"))
      (libsource (lib "eagle-import") (part "R0805_IPCGEN"))
    )
    (comp (ref "R216")
      (value "DNP")
      (footprint "eagle-import:0805_IPC-7351B")
      (fields (field (name "BOM") "EXCLUDE"))
      (libsource (lib "eagle-import") (part "R0805_IPCGEN"))
    )
    (comp (ref "R217")
      (value "330")
      (footprint "eagle-import:R2512")
      (libsource (lib "eagle-import") (part "R90R2512GEN"))
    )
    (comp (ref "R218")
      (value "270")
      (footprint "eagle-import:R2512")
      (libsource (lib "eagle-import") (part "R90R2512GEN"))
    )
    (comp (ref "R219")
      (value "330")
      (footprint "eagle-import:R2512")
      (libsource (lib "eagle-import") (part "R90R2512GEN"))
    )
    (comp (ref "R220")
      (value "270")
      (footprint "eagle-import:R2512")
      (libsource (lib "eagle-import") (part "R90R2512GEN"))
    )
    (comp (ref "R221")
      (value "2.7")
      (footprint "eagle-import:R2512")
      (libsource (lib "eagle-import") (part "RR2512GEN"))
    )
    (comp (ref "R222")
      (value "2.7")
      (footprint "eagle-import:R2512")
      (libsource (lib "eagle-import") (part "RR2512GEN"))
    )
    (comp (ref "R223")
      (value "2.7")
      (footprint "eagle-import:R2512")
      (libsource (lib "eagle-import") (part "RR2512GEN"))
    )
    (comp (ref "R224")
      (value "2.7")
      (footprint "eagle-import:R2512")
      (libsource (lib "eagle-import") (part "RR2512GEN"))
    )
    (comp (ref "R225")
      (value "2.7")
      (footprint "eagle-import:R2512")
      (libsource (lib "eagle-import") (part "RR2512GEN"))
    )
    (comp (ref "R226")
      (value "2.7")
      (footprint "eagle-import:R2512")
      (libsource (lib "eagle-import") (part "RR2512GEN"))
    )
    (comp (ref "R227")
      (value "3.3")
      (footprint "eagle-import:R2512")
      (libsource (lib "eagle-import") (part "RR2512GEN"))
    )
    (comp (ref "R228")
      (value "3.3")
      (footprint "eagle-import:R2512")
      (libsource (lib "eagle-import") (part "RR2512GEN"))
    )
    (comp (ref "R229")
      (value "1K")
      (footprint "eagle-import:0805_IPC-7351B")
      (libsource (lib "eagle-import") (part "R900805_IPCGEN"))
    )
    (comp (ref "R230")
      (value "1K")
      (footprint "eagle-import:0805_IPC-7351B")
      (libsource (lib "eagle-import") (part "R900805_IPCGEN"))
    )
    (comp (ref "TP7")
      (value "PROBE_TPTP_5MM")
      (footprint "eagle-import:PROBE_TP_5MM")
      (libsource (lib "eagle-import") (part "PROBE_TPTP_5MM"))
    )
    (comp (ref "TP8")
      (value "PROBE_TPTP_7P5MM")
      (footprint "eagle-import:PROBE_TP_7P5MM")
      (libsource (lib "eagle-import") (part "PROBE_TPTP_7P5MM"))
    )
    (comp (ref "TP9")
      (value "PROBE_TPTP_5MM")
      (footprint "eagle-import:PROBE_TP_5MM")
      (libsource (lib "eagle-import") (part "PROBE_TPTP_5MM"))
    )
    (comp (ref "TP10")
      (value "PROBE_TPTP_7P5MM")
      (footprint "eagle-import:PROBE_TP_7P5MM")
      (libsource (lib "eagle-import") (part "PROBE_TPTP_7P5MM"))
    )
    (comp (ref "TP16")
      (value "PROBE_TPTP_5MM")
      (footprint "eagle-import:PROBE_TP_5MM")
      (libsource (lib "eagle-import") (part "PROBE_TPTP_5MM"))
    )
    (comp (ref "TP17")
      (value "PROBE_TPTP_5MM")
      (footprint "eagle-import:PROBE_TP_5MM")
      (libsource (lib "eagle-import") (part "PROBE_TPTP_5MM"))
    )
    (comp (ref "C301")
      (value "0.1uF")
      (footprint "eagle-import:0805_IPC-7351B")
      (fields (field (name "VOLTAGE") "25V"))
      (libsource (lib "eagle-import") (part "C0805_IPCGEN"))
    )
    (comp (ref "C302")
      (value "DNP")
      (footprint "eagle-import:0805_IPC-7351B")
      (fields (field (name "PACKAGE") "0805") (field (name "BOM") "EXCLUDE") (field (name "VOLTAGE") "25V"))
      (libsource (lib "eagle-import") (part "C0805_IPCGEN"))
    )
    (comp (ref "C303")
      (value "DNP")
      (footprint "eagle-import:0805_IPC-7351B")
      (fields (field (name "BOM") "EXCLUDE") (field (name "VOLTAGE") "25V"))
      (libsource (lib "eagle-import") (part "C0805_IPCGEN"))
    )
    (comp (ref "C304")
      (value "33pF")
      (footprint "eagle-import:0805_IPC-7351B")
      (fields (field (name "VOLTAGE") "50V"))
      (libsource (lib "eagle-import") (part "C0805_IPCGEN"))
    )
    (comp (ref "C305")
      (value "0.1uF")
      (footprint "eagle-import:0805_IPC-7351B")
      (fields (field (name "VOLTAGE") "25V"))
      (libsource (lib "eagle-import") (part "C0805_IPCGEN"))
    )
    (comp (ref "C306")
      (value "0.1uF")
      (footprint "eagle-import:0805_IPC-7351B")
      (fields (field (name "VOLTAGE") "25V"))
      (libsource (lib "eagle-import") (part "C0805_IPCGEN"))
    )
    (comp (ref "J301")
      (value "COAX112640BNC_EDGE")
      (footprint "eagle-import:BNC_EDGE")
      (fields (field (name "PARTNO") "112640"))
      (libsource (lib "eagle-import") (part "COAXBNC_EDGE112640"))
    )
    (comp (ref "J302")
      (value "COAX112640BNC_EDGE")
      (footprint "eagle-import:BNC_EDGE")
      (fields (field (name "PARTNO") "112640"))
      (libsource (lib "eagle-import") (part "COAXBNC_EDGE112640"))
    )
    (comp (ref "JP301")
      (value "PINHD-1X2")
      (footprint "eagle-import:1X02")
      (libsource (lib "eagle-import") (part "PINHD-1X2"))
    )
    (comp (ref "JP302")
      (value "PINHD-1X2")
      (footprint "eagle-import:1X02")
      (libsource (lib "eagle-import") (part "PINHD-1X2"))
    )
    (comp (ref "LED301")
      (value "LEDHLMP-3401-E0002T1_3/4")
      (footprint "eagle-import:LED5MM")
      (fields (field (name "PARTNO") " HLMP-3401-E0002"))
      (libsource (lib "eagle-import") (part "LEDT1_3/4HLMP-3401-E0002"))
    )
    (comp (ref "Q301")
      (value "MOSFET_NBSS123SOT23")
      (footprint "eagle-import:SOT23R_INFINEON")
      (fields (field (name "PARTNO") "BSS123-7-F") (field (name "VOLTAGE") "100V"))
      (libsource (lib "eagle-import") (part "MOSFET_NSOT23BSS123"))
    )
    (comp (ref "Q302")
      (value "PNPSOT23_BEC")
      (footprint "eagle-import:SOT23R_INFINEON")
      (fields (field (name "VOLTAGE") "40V") (field (name "PARTNO") "PMBT3906,215"))
      (libsource (lib "eagle-import") (part "PNPSOT23_BEC"))
    )
    (comp (ref "Q303")
      (value "NPNMMBT3904SOT23_BEC")
      (footprint "eagle-import:SOT23R_INFINEON")
      (fields (field (name "PARTNO") "MMBT3904,215") (field (name "VOLTAGE") "40V"))
      (libsource (lib "eagle-import") (part "NPNSOT23_BECMMBT3904"))
    )
    (comp (ref "R301")
      (value "10K")
      (footprint "eagle-import:RTRIM3299W")
      (fields (field (name "PARTNO") "3299W-1-103LF") (field (name "POWER") "0.5W"))
      (libsource (lib "eagle-import") (part "RTRIM3299WRTRIM-10K-10%-3299W-0.5W"))
    )
    (comp (ref "R302")
      (value "10K")
      (footprint "eagle-import:0805_IPC-7351B")
      (libsource (lib "eagle-import") (part "R900805_IPCGEN"))
    )
    (comp (ref "R303")
      (value "10K")
      (footprint "eagle-import:0805_IPC-7351B")
      (libsource (lib "eagle-import") (part "R900805_IPCGEN"))
    )
    (comp (ref "R304")
      (value "1K")
      (footprint "eagle-import:0805_IPC-7351B")
      (libsource (lib "eagle-import") (part "R900805_IPCGEN"))
    )
    (comp (ref "R305")
      (value "10K")
      (footprint "eagle-import:0805_IPC-7351B")
      (libsource (lib "eagle-import") (part "R900805_IPCGEN"))
    )
    (comp (ref "R306")
      (value "10K")
      (footprint "eagle-import:0805_IPC-7351B")
      (libsource (lib "eagle-import") (part "R900805_IPCGEN"))
    )
    (comp (ref "R307")
      (value "100K")
      (footprint "eagle-import:0805_IPC-7351B")
      (libsource (lib "eagle-import") (part "R0805_IPCGEN"))
    )
    (comp (ref "R308")
      (value "1K")
      (footprint "eagle-import:0805_IPC-7351B")
      (libsource (lib "eagle-import") (part "R900805_IPCGEN"))
    )
    (comp (ref "R309")
      (value "150")
      (footprint "eagle-import:0805_IPC-7351B")
      (libsource (lib "eagle-import") (part "R0805_IPCGEN"))
    )
    (comp (ref "R310")
      (value "1K")
      (footprint "eagle-import:0805_IPC-7351B")
      (libsource (lib "eagle-import") (part "R900805_IPCGEN"))
    )
    (comp (ref "R311")
      (value "DNP")
      (footprint "eagle-import:0805_IPC-7351B")
      (fields (field (name "BOM") "EXCLUDE"))
      (libsource (lib "eagle-import") (part "R0805_IPCGEN"))
    )
    (comp (ref "R312")
      (value "10K")
      (footprint "eagle-import:0805_IPC-7351B")
      (libsource (lib "eagle-import") (part "R900805_IPCGEN"))
    )
    (comp (ref "R313")
      (value "DNP")
      (footprint "eagle-import:0805_IPC-7351B")
      (fields (field (name "BOM") "EXCLUDE"))
      (libsource (lib "eagle-import") (part "R900805_IPCGEN"))
    )
    (comp (ref "R314")
      (value "0")
      (footprint "eagle-import:0805_IPC-7351B")
      (libsource (lib "eagle-import") (part "R0805_IPCGEN"))
    )
    (comp (ref "R315")
      (value "10")
      (footprint "eagle-import:0805_IPC-7351B")
      (libsource (lib "eagle-import") (part "R900805_IPCGEN"))
    )
    (comp (ref "R316")
      (value "100")
      (footprint "eagle-import:0805_IPC-7351B")
      (libsource (lib "eagle-import") (part "R900805_IPCGEN"))
    )
    (comp (ref "R317")
      (value "10K")
      (footprint "eagle-import:0805_IPC-7351B")
      (libsource (lib "eagle-import") (part "R900805_IPCGEN"))
    )
    (comp (ref "TP11")
      (value "PROBE_TPTP_5MM")
      (footprint "eagle-import:PROBE_TP_5MM")
      (libsource (lib "eagle-import") (part "PROBE_TPTP_5MM"))
    )
    (comp (ref "TP12")
      (value "PROBE_TPTP_5MM")
      (footprint "eagle-import:PROBE_TP_5MM")
      (libsource (lib "eagle-import") (part "PROBE_TPTP_5MM"))
    )
    (comp (ref "TP13")
      (value "PROBE_TPTP_5MM")
      (footprint "eagle-import:PROBE_TP_5MM")
      (libsource (lib "eagle-import") (part "PROBE_TPTP_5MM"))
    )
    (comp (ref "U301")
      (value "74AHC1G14DBV")
      (footprint "eagle-import:SOT23-5")
      (description "IC INVERT SCHMITT 1CH 1-IN SOT25")
      (fields
        (field (name "PARTNO") "74AHC1G14QW5-7")
        (field (name "BOM") "INCLUDE")
        (field (name "PACKAGE") "SOT23-5")
        (field (name "VENDOR") "Diodes Inc")
      )
      (libsource (lib "eagle-import") (part "741G14DBVAHC"))
    )
    (comp (ref "U302")
      (value "OPAMP_QUADTLV274IDSOIC14")
      (footprint "eagle-import:SO14")
      (fields (field (name "PARTNO") "TLV274ID"))
      (libsource (lib "eagle-import") (part "OPAMP_QUADSOIC14TLV274ID"))
    )
  )
  (nets
    (net (code "1") (name "+5V") (class "Default")
      (node (ref "C306") (pin "1") (pinfunction "1_1") (pintype "passive"))
      (node (ref "C407") (pin "1") (pinfunction "1_1") (pintype "passive"))
      (node (ref "C410") (pin "+") (pinfunction "+_+") (pintype "passive"))
      (node (ref "LED301") (pin "A") (pinfunction "A_A") (pintype "passive"))
      (node (ref "LED402") (pin "A") (pinfunction "A_A") (pintype "passive"))
      (node (ref "R301") (pin "3") (pinfunction "E_3") (pintype "passive"))
      (node (ref "R408") (pin "1") (pinfunction "1_1") (pintype "passive"))
      (node (ref "U301") (pin "5") (pinfunction "VCC_5") (pintype "power_in"))
      (node (ref "U402") (pin "3") (pinfunction "OUT_3") (pintype "passive"))
    )
    (net (code "2") (name "ABN1") (class "Default")
      (node (ref "R103") (pin "1") (pinfunction "1_1") (pintype "passive"))
      (node (ref "R105") (pin "1") (pinfunction "1_1") (pintype "passive"))
      (node (ref "R202") (pin "1") (pinfunction "1_1") (pintype "passive"))
      (node (ref "R204") (pin "1") (pinfunction "1_1") (pintype "passive"))
      (node (ref "T101") (pin "11") (pinfunction "F2_11") (pintype "passive"))
      (node (ref "TP18") (pin "TP") (pinfunction "1_TP") (pintype "passive"))
    )
    (net (code "3") (name "ABP1") (class "Default")
      (node (ref "R102") (pin "1") (pinfunction "1_1") (pintype "passive"))
      (node (ref "R104") (pin "1") (pinfunction "1_1") (pintype "passive"))
      (node (ref "R201") (pin "1") (pinfunction "1_1") (pintype "passive"))
      (node (ref "R203") (pin "1") (pinfunction "1_1") (pintype "passive"))
      (node (ref "T101") (pin "1") (pinfunction "S1_1") (pintype "passive"))
      (node (ref "TP19") (pin "TP") (pinfunction "1_TP") (pintype "passive"))
    )
    (net (code "4") (name "AN2") (class "Default")
      (node (ref "C107") (pin "2") (pinfunction "2_2") (pintype "passive"))
      (node (ref "R105") (pin "2") (pinfunction "2_2") (pintype "passive"))
      (node (ref "R107") (pin "1") (pinfunction "1_1") (pintype "passive"))
    )
    (net (code "5") (name "AN3") (class "Default")
      (node (ref "C107") (pin "1") (pinfunction "1_1") (pintype "passive"))
      (node (ref "L102") (pin "1") (pinfunction "1_1") (pintype "passive"))
      (node (ref "R111") (pin "2") (pinfunction "2_2") (pintype "passive"))
      (node (ref "R113") (pin "1") (pinfunction "1_1") (pintype "passive"))
      (node (ref "R115") (pin "1") (pinfunction "1_1") (pintype "passive"))
    )
    (net (code "6") (name "AN4") (class "Default")
      (node (ref "L102") (pin "2") (pinfunction "2_2") (pintype "passive"))
      (node (ref "Q102") (pin "G") (pinfunction "G_G") (pintype "passive"))
      (node (ref "R115") (pin "2") (pinfunction "2_2") (pintype "passive"))
      (node (ref "R117") (pin "1") (pinfunction "1_1") (pintype "passive"))
      (node (ref "R120") (pin "1") (pinfunction "1_1") (pintype "passive"))
      (node (ref "R121") (pin "1") (pinfunction "1_1") (pintype "passive"))
      (node (ref "TP3") (pin "TP") (pinfunction "1_TP") (pintype "passive"))
    )
    (net (code "7") (name "AN5") (class "Default")
      (node (ref "Q102") (pin "S") (pinfunction "S_S") (pintype "passive"))
      (node (ref "R123") (pin "1") (pinfunction "1_1") (pintype "passive"))
      (node (ref "R125") (pin "1") (pinfunction "1_1") (pintype "passive"))
      (node (ref "R127") (pin "1") (pinfunction "1_1") (pintype "passive"))
      (node (ref "R129") (pin "1") (pinfunction "1_1") (pintype "passive"))
      (node (ref "R131") (pin "1") (pinfunction "1_1") (pintype "passive"))
      (node (ref "TP6") (pin "TP") (pinfunction "1_TP") (pintype "passive"))
    )
    (net (code "8") (name "AN6") (class "Default")
      (node (ref "C115") (pin "1") (pinfunction "1_1") (pintype "passive"))
      (node (ref "R131") (pin "2") (pinfunction "2_2") (pintype "passive"))
      (node (ref "TP15") (pin "TP") (pinfunction "1_TP") (pintype "passive"))
    )
    (net (code "9") (name "AP2") (class "Default")
      (node (ref "C105") (pin "2") (pinfunction "2_2") (pintype "passive"))
      (node (ref "R104") (pin "2") (pinfunction "2_2") (pintype "passive"))
      (node (ref "R106") (pin "1") (pinfunction "1_1") (pintype "passive"))
    )
    (net (code "10") (name "AP3") (class "Default")
      (node (ref "C105") (pin "1") (pinfunction "1_1") (pintype "passive"))
      (node (ref "L101") (pin "1") (pinfunction "1_1") (pintype "passive"))
      (node (ref "R109") (pin "2") (pinfunction "2_2") (pintype "passive"))
      (node (ref "R112") (pin "1") (pinfunction "1_1") (pintype "passive"))
      (node (ref "R114") (pin "1") (pinfunction "1_1") (pintype "passive"))
    )
    (net (code "11") (name "AP4") (class "Default")
      (node (ref "L101") (pin "2") (pinfunction "2_2") (pintype "passive"))
      (node (ref "Q101") (pin "G") (pinfunction "G_G") (pintype "passive"))
      (node (ref "R114") (pin "2") (pinfunction "2_2") (pintype "passive"))
      (node (ref "R116") (pin "1") (pinfunction "1_1") (pintype "passive"))
      (node (ref "R118") (pin "1") (pinfunction "1_1") (pintype "passive"))
      (node (ref "R119") (pin "1") (pinfunction "1_1") (pintype "passive"))
      (node (ref "TP1") (pin "TP") (pinfunction "1_TP") (pintype "passive"))
    )
    (net (code "12") (name "AP5") (class "Default")
      (node (ref "Q101") (pin "S") (pinfunction "S_S") (pintype "passive"))
      (node (ref "R122") (pin "1") (pinfunction "1_1") (pintype "passive"))
      (node (ref "R124") (pin "1") (pinfunction "1_1") (pintype "passive"))
      (node (ref "R126") (pin "1") (pinfunction "1_1") (pintype "passive"))
      (node (ref "R128") (pin "1") (pinfunction "1_1") (pintype "passive"))
      (node (ref "R130") (pin "1") (pinfunction "1_1") (pintype "passive"))
      (node (ref "TP5") (pin "TP") (pinfunction "1_TP") (pintype "passive"))
    )
    (net (code "13") (name "AP6") (class "Default")
      (node (ref "C114") (pin "1") (pinfunction "1_1") (pintype "passive"))
      (node (ref "R130") (pin "2") (pinfunction "2_2") (pintype "passive"))
      (node (ref "TP14") (pin "TP") (pinfunction "1_TP") (pintype "passive"))
    )
    (net (code "14") (name "BN2") (class "Default")
      (node (ref "C204") (pin "2") (pinfunction "2_2") (pintype "passive"))
      (node (ref "R204") (pin "2") (pinfunction "2_2") (pintype "passive"))
      (node (ref "R206") (pin "1") (pinfunction "1_1") (pintype "passive"))
    )
    (net (code "15") (name "BN3") (class "Default")
      (node (ref "C204") (pin "1") (pinfunction "1_1") (pintype "passive"))
      (node (ref "L202") (pin "1") (pinfunction "1_1") (pintype "passive"))
      (node (ref "R210") (pin "2") (pinfunction "2_2") (pintype "passive"))
      (node (ref "R212") (pin "1") (pinfunction "1_1") (pintype "passive"))
      (node (ref "R214") (pin "1") (pinfunction "1_1") (pintype "passive"))
    )
    (net (code "16") (name "BN4") (class "Default")
      (node (ref "L202") (pin "2") (pinfunction "2_2") (pintype "passive"))
      (node (ref "Q202") (pin "G") (pinfunction "G_G") (pintype "passive"))
      (node (ref "R214") (pin "2") (pinfunction "2_2") (pintype "passive"))
      (node (ref "R216") (pin "1") (pinfunction "1_1") (pintype "passive"))
      (node (ref "R219") (pin "1") (pinfunction "1_1") (pintype "passive"))
      (node (ref "R220") (pin "1") (pinfunction "1_1") (pintype "passive"))
      (node (ref "TP9") (pin "TP") (pinfunction "1_TP") (pintype "passive"))
    )
    (net (code "17") (name "BN5") (class "Default")
      (node (ref "Q202") (pin "S") (pinfunction "S_S") (pintype "passive"))
      (node (ref "R222") (pin "1") (pinfunction "1_1") (pintype "passive"))
      (node (ref "R224") (pin "1") (pinfunction "1_1") (pintype "passive"))
      (node (ref "R226") (pin "1") (pinfunction "1_1") (pintype "passive"))
      (node (ref "R228") (pin "1") (pinfunction "1_1") (pintype "passive"))
      (node (ref "R230") (pin "1") (pinfunction "1_1") (pintype "passive"))
      (node (ref "TP10") (pin "TP") (pinfunction "1_TP") (pintype "passive"))
    )
    (net (code "18") (name "BN6") (class "Default")
      (node (ref "C212") (pin "1") (pinfunction "1_1") (pintype "passive"))
      (node (ref "R230") (pin "2") (pinfunction "2_2") (pintype "passive"))
      (node (ref "TP17") (pin "TP") (pinfunction "1_TP") (pintype "passive"))
    )
    (net (code "19") (name "BP2") (class "Default")
      (node (ref "C202") (pin "2") (pinfunction "2_2") (pintype "passive"))
      (node (ref "R203") (pin "2") (pinfunction "2_2") (pintype "passive"))
      (node (ref "R205") (pin "1") (pinfunction "1_1") (pintype "passive"))
    )
    (net (code "20") (name "BP3") (class "Default")
      (node (ref "C202") (pin "1") (pinfunction "1_1") (pintype "passive"))
      (node (ref "L201") (pin "1") (pinfunction "1_1") (pintype "passive"))
      (node (ref "R208") (pin "2") (pinfunction "2_2") (pintype "passive"))
      (node (ref "R211") (pin "1") (pinfunction "1_1") (pintype "passive"))
      (node (ref "R213") (pin "1") (pinfunction "1_1") (pintype "passive"))
    )
    (net (code "21") (name "BP4") (class "Default")
      (node (ref "L201") (pin "2") (pinfunction "2_2") (pintype "passive"))
      (node (ref "Q201") (pin "G") (pinfunction "G_G") (pintype "passive"))
      (node (ref "R213") (pin "2") (pinfunction "2_2") (pintype "passive"))
      (node (ref "R215") (pin "1") (pinfunction "1_1") (pintype "passive"))
      (node (ref "R217") (pin "1") (pinfunction "1_1") (pintype "passive"))
      (node (ref "R218") (pin "1") (pinfunction "1_1") (pintype "passive"))
      (node (ref "TP7") (pin "TP") (pinfunction "1_TP") (pintype "passive"))
    )
    (net (code "22") (name "BP5") (class "Default")
      (node (ref "Q201") (pin "S") (pinfunction "S_S") (pintype "passive"))
      (node (ref "R221") (pin "1") (pinfunction "1_1") (pintype "passive"))
      (node (ref "R223") (pin "1") (pinfunction "1_1") (pintype "passive"))
      (node (ref "R225") (pin "1") (pinfunction "1_1") (pintype "passive"))
      (node (ref "R227") (pin "1") (pinfunction "1_1") (pintype "passive"))
      (node (ref "R229") (pin "1") (pinfunction "1_1") (pintype "passive"))
      (node (ref "TP8") (pin "TP") (pinfunction "1_TP") (pintype "passive"))
    )
    (net (code "23") (name "BP6") (class "Default")
      (node (ref "C211") (pin "1") (pinfunction "1_1") (pintype "passive"))
      (node (ref "R229") (pin "2") (pinfunction "2_2") (pintype "passive"))
      (node (ref "TP16") (pin "TP") (pinfunction "1_TP") (pintype "passive"))
    )
    (net (code "24") (name "DRAINS_NEG") (class "Default")
      (node (ref "C113") (pin "2") (pinfunction "2_2") (pintype "passive"))
      (node (ref "C117") (pin "2") (pinfunction "2_2") (pintype "passive"))
      (node (ref "C210") (pin "2") (pinfunction "2_2") (pintype "passive"))
      (node (ref "L104") (pin "1") (pinfunction "1_1") (pintype "passive"))
      (node (ref "Q102") (pin "D") (pinfunction "D_D") (pintype "passive"))
      (node (ref "Q202") (pin "D") (pinfunction "D_D") (pintype "passive"))
      (node (ref "T102") (pin "8") (pinfunction "F5_8") (pintype "passive"))
      (node (ref "TP4") (pin "TP") (pinfunction "1_TP") (pintype "passive"))
    )
    (net (code "25") (name "DRAINS_POS") (class "Default")
      (node (ref "C112") (pin "2") (pinfunction "2_2") (pintype "passive"))
      (node (ref "C116") (pin "2") (pinfunction "2_2") (pintype "passive"))
      (node (ref "C209") (pin "2") (pinfunction "2_2") (pintype "passive"))
      (node (ref "L103") (pin "1") (pinfunction "1_1") (pintype "passive"))
      (node (ref "Q101") (pin "D") (pinfunction "D_D") (pintype "passive"))
      (node (ref "Q201") (pin "D") (pinfunction "D_D") (pintype "passive"))
      (node (ref "T102") (pin "6") (pinfunction "S6_6") (pintype "passive"))
      (node (ref "TP2") (pin "TP") (pinfunction "1_TP") (pintype "passive"))
    )
    (net (code "26") (name "GBIAS") (class "Default")
      (node (ref "Q302") (pin "2") (pinfunction "E_2") (pintype "passive"))
      (node (ref "Q303") (pin "2") (pinfunction "E_2") (pintype "passive"))
      (node (ref "R108") (pin "1") (pinfunction "1_1") (pintype "passive"))
      (node (ref "R110") (pin "1") (pinfunction "1_1") (pintype "passive"))
      (node (ref "R207") (pin "1") (pinfunction "1_1") (pintype "passive"))
      (node (ref "R209") (pin "1") (pinfunction "1_1") (pintype "passive"))
      (node (ref "R316") (pin "2") (pinfunction "2_2") (pintype "passive"))
      (node (ref "R317") (pin "2") (pinfunction "2_2") (pintype "passive"))
      (node (ref "TP11") (pin "TP") (pinfunction "1_TP") (pintype "passive"))
    )
    (net (code "27") (name "Net-(C104-Pad1)") (class "Default")
      (node (ref "C104") (pin "1") (pinfunction "1_1") (pintype "passive"))
      (node (ref "R108") (pin "2") (pinfunction "2_2") (pintype "passive"))
      (node (ref "R109") (pin "1") (pinfunction "1_1") (pintype "passive"))
    )
    (net (code "28") (name "Net-(C106-Pad1)") (class "Default")
      (node (ref "C106") (pin "1") (pinfunction "1_1") (pintype "passive"))
      (node (ref "R110") (pin "2") (pinfunction "2_2") (pintype "passive"))
      (node (ref "R111") (pin "1") (pinfunction "1_1") (pintype "passive"))
    )
    (net (code "29") (name "Net-(C108-Pad1)") (class "Default")
      (node (ref "C108") (pin "1") (pinfunction "1_1") (pintype "passive"))
      (node (ref "R112") (pin "2") (pinfunction "2_2") (pintype "passive"))
    )
    (net (code "30") (name "Net-(C109-Pad1)") (class "Default")
      (node (ref "C109") (pin "1") (pinfunction "1_1") (pintype "passive"))
      (node (ref "R113") (pin "2") (pinfunction "2_2") (pintype "passive"))
    )
    (net (code "31") (name "Net-(C110-Pad1)") (class "Default")
      (node (ref "C110") (pin "1") (pinfunction "1_1") (pintype "passive"))
      (node (ref "R116") (pin "2") (pinfunction "2_2") (pintype "passive"))
    )
    (net (code "32") (name "Net-(C111-Pad1)") (class "Default")
      (node (ref "C111") (pin "1") (pinfunction "1_1") (pintype "passive"))
      (node (ref "R117") (pin "2") (pinfunction "2_2") (pintype "passive"))
    )
    (net (code "33") (name "Net-(C112-Pad1)") (class "Default")
      (node (ref "C112") (pin "1") (pinfunction "1_1") (pintype "passive"))
      (node (ref "R118") (pin "2") (pinfunction "2_2") (pintype "passive"))
      (node (ref "R119") (pin "2") (pinfunction "2_2") (pintype "passive"))
    )
    (net (code "34") (name "Net-(C113-Pad1)") (class "Default")
      (node (ref "C113") (pin "1") (pinfunction "1_1") (pintype "passive"))
      (node (ref "R120") (pin "2") (pinfunction "2_2") (pintype "passive"))
      (node (ref "R121") (pin "2") (pinfunction "2_2") (pintype "passive"))
    )
    (net (code "35") (name "Net-(C201-Pad1)") (class "Default")
      (node (ref "C201") (pin "1") (pinfunction "1_1") (pintype "passive"))
      (node (ref "R207") (pin "2") (pinfunction "2_2") (pintype "passive"))
      (node (ref "R208") (pin "1") (pinfunction "1_1") (pintype "passive"))
    )
    (net (code "36") (name "Net-(C203-Pad1)") (class "Default")
      (node (ref "C203") (pin "1") (pinfunction "1_1") (pintype "passive"))
      (node (ref "R209") (pin "2") (pinfunction "2_2") (pintype "passive"))
      (node (ref "R210") (pin "1") (pinfunction "1_1") (pintype "passive"))
    )
    (net (code "37") (name "Net-(C205-Pad1)") (class "Default")
      (node (ref "C205") (pin "1") (pinfunction "1_1") (pintype "passive"))
      (node (ref "R211") (pin "2") (pinfunction "2_2") (pintype "passive"))
    )
    (net (code "38") (name "Net-(C206-Pad1)") (class "Default")
      (node (ref "C206") (pin "1") (pinfunction "1_1") (pintype "passive"))
      (node (ref "R212") (pin "2") (pinfunction "2_2") (pintype "passive"))
    )
    (net (code "39") (name "Net-(C207-Pad1)") (class "Default")
      (node (ref "C207") (pin "1") (pinfunction "1_1") (pintype "passive"))
      (node (ref "R215") (pin "2") (pinfunction "2_2") (pintype "passive"))
    )
    (net (code "40") (name "Net-(C208-Pad1)") (class "Default")
      (node (ref "C208") (pin "1") (pinfunction "1_1") (pintype "passive"))
      (node (ref "R216") (pin "2") (pinfunction "2_2") (pintype "passive"))
    )
    (net (code "41") (name "Net-(C209-Pad1)") (class "Default")
      (node (ref "C209") (pin "1") (pinfunction "1_1") (pintype "passive"))
      (node (ref "R217") (pin "2") (pinfunction "2_2") (pintype "passive"))
      (node (ref "R218") (pin "2") (pinfunction "2_2") (pintype "passive"))
    )
    (net (code "42") (name "Net-(C210-Pad1)") (class "Default")
      (node (ref "C210") (pin "1") (pinfunction "1_1") (pintype "passive"))
      (node (ref "R219") (pin "2") (pinfunction "2_2") (pintype "passive"))
      (node (ref "R220") (pin "2") (pinfunction "2_2") (pintype "passive"))
    )
    (net (code "43") (name "Net-(C302-Pad1)") (class "Default")
      (node (ref "C302") (pin "1") (pinfunction "1_1") (pintype "passive"))
      (node (ref "R313") (pin "1") (pinfunction "1_1") (pintype "passive"))
    )
    (net (code "44") (name "Net-(C304-Pad1)") (class "Default")
      (node (ref "C304") (pin "1") (pinfunction "1_1") (pintype "passive"))
      (node (ref "R314") (pin "2") (pinfunction "2_2") (pintype "passive"))
    )
    (net (code "45") (name "Net-(C405-Pad1)") (class "Default")
      (node (ref "C405") (pin "1") (pinfunction "1_1") (pintype "passive"))
      (node (ref "L401") (pin "2") (pinfunction "2_2") (pintype "passive"))
      (node (ref "L402") (pin "1") (pinfunction "1_1") (pintype "passive"))
      (node (ref "R404") (pin "1") (pinfunction "1_1") (pintype "passive"))
      (node (ref "R405") (pin "1") (pinfunction "1_1") (pintype "passive"))
    )
    (net (code "46") (name "Net-(D401-C1)") (class "Default")
      (node (ref "D401") (pin "K") (pinfunction "C1_K") (pintype "passive"))
      (node (ref "F401") (pin "2") (pinfunction "2_2") (pintype "passive"))
      (node (ref "R401") (pin "1") (pinfunction "1_1") (pintype "passive"))
    )
    (net (code "47") (name "Net-(D402-A1)") (class "Default")
      (node (ref "D402") (pin "A") (pinfunction "A1_A") (pintype "passive"))
      (node (ref "R402") (pin "1") (pinfunction "1_1") (pintype "passive"))
      (node (ref "R403") (pin "1") (pinfunction "1_1") (pintype "passive"))
    )
    (net (code "48") (name "Net-(D402-C1)") (class "Default")
      (node (ref "C401") (pin "+") (pinfunction "+_+") (pintype "passive"))
      (node (ref "C402") (pin "1") (pinfunction "1_1") (pintype "passive"))
      (node (ref "D402") (pin "C") (pinfunction "C1_C") (pintype "passive"))
      (node (ref "L401") (pin "1") (pinfunction "1_1") (pintype "passive"))
      (node (ref "R401") (pin "2") (pinfunction "2_2") (pintype "passive"))
    )
    (net (code "49") (name "Net-(F401-Pad1)") (class "Default")
      (node (ref "F401") (pin "1") (pinfunction "1_1") (pintype "passive"))
      (node (ref "J401") (pin "1") (pinfunction "1_1") (pintype "passive"))
    )
    (net (code "50") (name "Net-(J101-1)") (class "Default")
      (node (ref "C101") (pin "2") (pinfunction "2_2") (pintype "passive"))
      (node (ref "C102") (pin "2") (pinfunction "2_2") (pintype "passive"))
      (node (ref "C103") (pin "2") (pinfunction "2_2") (pintype "passive"))
      (node (ref "J101") (pin "C") (pinfunction "1_C") (pintype "passive"))
    )
    (net (code "51") (name "Net-(J102-1)") (class "Default")
      (node (ref "C118") (pin "2") (pinfunction "2_2") (pintype "passive"))
      (node (ref "C119") (pin "2") (pinfunction "2_2") (pintype "passive"))
      (node (ref "C120") (pin "2") (pinfunction "2_2") (pintype "passive"))
      (node (ref "J102") (pin "C") (pinfunction "1_C") (pintype "passive"))
    )
    (net (code "52") (name "Net-(J301-1)") (class "Default")
      (node (ref "J301") (pin "C") (pinfunction "1_C") (pintype "passive"))
      (node (ref "JP301") (pin "2") (pinfunction "2_2") (pintype "passive"))
      (node (ref "R302") (pin "1") (pinfunction "1_1") (pintype "passive"))
    )
    (net (code "53") (name "Net-(J301-GND1-PadG1)") (class "Default")
      (node (ref "J301") (pin "G1") (pinfunction "GND1_G1") (pintype "power_in"))
      (node (ref "J301") (pin "G2") (pinfunction "GND1_G2") (pintype "power_in"))
      (node (ref "J301") (pin "G3") (pinfunction "GND1_G3") (pintype "power_in"))
      (node (ref "J301") (pin "G4") (pinfunction "GND1_G4") (pintype "power_in"))
      (node (ref "JP301") (pin "1") (pinfunction "1_1") (pintype "passive"))
      (node (ref "R303") (pin "1") (pinfunction "1_1") (pintype "passive"))
    )
    (net (code "54") (name "Net-(J302-1)") (class "Default")
      (node (ref "J302") (pin "C") (pinfunction "1_C") (pintype "passive"))
      (node (ref "R304") (pin "1") (pinfunction "1_1") (pintype "passive"))
    )
    (net (code "55") (name "Net-(J402-Pad3)") (class "Default")
      (node (ref "J402") (pin "3") (pinfunction "3_3") (pintype "passive"))
      (node (ref "R408") (pin "2") (pinfunction "2_2") (pintype "passive"))
    )
    (net (code "56") (name "Net-(LED301-C)") (class "Default")
      (node (ref "LED301") (pin "K") (pinfunction "C_K") (pintype "passive"))
      (node (ref "R309") (pin "1") (pinfunction "1_1") (pintype "passive"))
    )
    (net (code "57") (name "Net-(LED401-C)") (class "Default")
      (node (ref "LED401") (pin "K") (pinfunction "C_K") (pintype "passive"))
      (node (ref "R406") (pin "1") (pinfunction "1_1") (pintype "passive"))
    )
    (net (code "58") (name "Net-(LED402-C)") (class "Default")
      (node (ref "LED402") (pin "K") (pinfunction "C_K") (pintype "passive"))
      (node (ref "R407") (pin "1") (pinfunction "1_1") (pintype "passive"))
    )
    (net (code "59") (name "Net-(Q301-D)") (class "Default")
      (node (ref "Q301") (pin "3") (pinfunction "D_3") (pintype "passive"))
      (node (ref "R308") (pin "2") (pinfunction "2_2") (pintype "passive"))
      (node (ref "U302") (pin "5") (pinfunction "+IN_5") (pintype "input"))
    )
    (net (code "60") (name "Net-(Q301-G)") (class "Default")
      (node (ref "Q301") (pin "1") (pinfunction "G_1") (pintype "passive"))
      (node (ref "R309") (pin "2") (pinfunction "2_2") (pintype "passive"))
      (node (ref "U301") (pin "4") (pinfunction "O_4") (pintype "output"))
    )
    (net (code "61") (name "Net-(Q302-B)") (class "Default")
      (node (ref "Q302") (pin "1") (pinfunction "B_1") (pintype "passive"))
      (node (ref "Q303") (pin "1") (pinfunction "B_1") (pintype "passive"))
      (node (ref "R315") (pin "2") (pinfunction "2_2") (pintype "passive"))
      (node (ref "R316") (pin "1") (pinfunction "1_1") (pintype "passive"))
    )
    (net (code "62") (name "Net-(R301-S)") (class "Default")
      (node (ref "C301") (pin "1") (pinfunction "1_1") (pintype "passive"))
      (node (ref "R301") (pin "2") (pinfunction "S_2") (pintype "passive"))
      (node (ref "U302") (pin "12") (pinfunction "+IN_12") (pintype "input"))
    )
    (net (code "63") (name "Net-(T101-F1)") (class "Default")
      (node (ref "R101") (pin "1") (pinfunction "1_1") (pintype "passive"))
      (node (ref "T101") (pin "12") (pinfunction "F1_12") (pintype "passive"))
      (node (ref "T101") (pin "2") (pinfunction "S2_2") (pintype "passive"))
    )
    (net (code "64") (name "Net-(T101-F4)") (class "Default")
      (node (ref "T101") (pin "3") (pinfunction "S3_3") (pintype "passive"))
      (node (ref "T101") (pin "9") (pinfunction "F4_9") (pintype "passive"))
    )
    (net (code "65") (name "Net-(T101-F5)") (class "Default")
      (node (ref "C101") (pin "1") (pinfunction "1_1") (pintype "passive"))
      (node (ref "T101") (pin "4") (pinfunction "S4_4") (pintype "passive"))
      (node (ref "T101") (pin "8") (pinfunction "F5_8") (pintype "passive"))
    )
    (net (code "66") (name "Net-(T101-F6)") (class "Default")
      (node (ref "C102") (pin "1") (pinfunction "1_1") (pintype "passive"))
      (node (ref "T101") (pin "5") (pinfunction "S5_5") (pintype "passive"))
      (node (ref "T101") (pin "7") (pinfunction "F6_7") (pintype "passive"))
    )
    (net (code "67") (name "Net-(T101-S6)") (class "Default")
      (node (ref "C103") (pin "1") (pinfunction "1_1") (pintype "passive"))
      (node (ref "T101") (pin "6") (pinfunction "S6_6") (pintype "passive"))
    )
    (net (code "68") (name "Net-(T102-F1)") (class "Default")
      (node (ref "C119") (pin "1") (pinfunction "1_1") (pintype "passive"))
      (node (ref "T102") (pin "12") (pinfunction "F1_12") (pintype "passive"))
      (node (ref "T102") (pin "2") (pinfunction "S2_2") (pintype "passive"))
    )
    (net (code "69") (name "Net-(T102-F2)") (class "Default")
      (node (ref "C118") (pin "1") (pinfunction "1_1") (pintype "passive"))
      (node (ref "T102") (pin "11") (pinfunction "F2_11") (pintype "passive"))
      (node (ref "T102") (pin "3") (pinfunction "S3_3") (pintype "passive"))
    )
    (net (code "70") (name "Net-(T102-F3)") (class "Default")
      (node (ref "T102") (pin "10") (pinfunction "F3_10") (pintype "passive"))
      (node (ref "T102") (pin "4") (pinfunction "S4_4") (pintype "passive"))
    )
    (net (code "71") (name "Net-(T102-F6)") (class "Default")
      (node (ref "R132") (pin "2") (pinfunction "2_2") (pintype "passive"))
      (node (ref "T102") (pin "5") (pinfunction "S5_5") (pintype "passive"))
      (node (ref "T102") (pin "7") (pinfunction "F6_7") (pintype "passive"))
    )
    (net (code "72") (name "Net-(T102-S1)") (class "Default")
      (node (ref "C120") (pin "1") (pinfunction "1_1") (pintype "passive"))
      (node (ref "T102") (pin "1") (pinfunction "S1_1") (pintype "passive"))
    )
    (net (code "73") (name "Net-(TP12-1)") (class "Default")
      (node (ref "R310") (pin "1") (pinfunction "1_1") (pintype "passive"))
      (node (ref "TP12") (pin "TP") (pinfunction "1_TP") (pintype "passive"))
      (node (ref "U302") (pin "6") (pinfunction "-IN_6") (pintype "input"))
      (node (ref "U302") (pin "7") (pinfunction "OUT_7") (pintype "output"))
    )
    (net (code "74") (name "Net-(TP13-1)") (class "Default")
      (node (ref "R306") (pin "2") (pinfunction "2_2") (pintype "passive"))
      (node (ref "TP13") (pin "TP") (pinfunction "1_TP") (pintype "passive"))
      (node (ref "U302") (pin "13") (pinfunction "-IN_13") (pintype "input"))
      (node (ref "U302") (pin "14") (pinfunction "OUT_14") (pintype "output"))
    )
    (net (code "75") (name "Net-(U301A-I)") (class "Default")
      (node (ref "R304") (pin "2") (pinfunction "2_2") (pintype "passive"))
      (node (ref "R307") (pin "1") (pinfunction "1_1") (pintype "passive"))
      (node (ref "U301") (pin "2") (pinfunction "I_2") (pintype "input"))
    )
    (net (code "76") (name "Net-(U302A-+IN)") (class "Default")
      (node (ref "C303") (pin "1") (pinfunction "1_1") (pintype "passive"))
      (node (ref "R310") (pin "2") (pinfunction "2_2") (pintype "passive"))
      (node (ref "R311") (pin "1") (pinfunction "1_1") (pintype "passive"))
      (node (ref "U302") (pin "3") (pinfunction "+IN_3") (pintype "input"))
    )
    (net (code "77") (name "Net-(U302A--IN)") (class "Default")
      (node (ref "C304") (pin "2") (pinfunction "2_2") (pintype "passive"))
      (node (ref "R312") (pin "2") (pinfunction "2_2") (pintype "passive"))
      (node (ref "R313") (pin "2") (pinfunction "2_2") (pintype "passive"))
      (node (ref "R317") (pin "1") (pinfunction "1_1") (pintype "passive"))
      (node (ref "U302") (pin "2") (pinfunction "-IN_2") (pintype "input"))
    )
    (net (code "78") (name "Net-(U302A-OUT)") (class "Default")
      (node (ref "R314") (pin "1") (pinfunction "1_1") (pintype "passive"))
      (node (ref "R315") (pin "1") (pinfunction "1_1") (pintype "passive"))
      (node (ref "U302") (pin "1") (pinfunction "OUT_1") (pintype "output"))
    )
    (net (code "79") (name "Net-(U302C-+IN)") (class "Default")
      (node (ref "R303") (pin "2") (pinfunction "2_2") (pintype "passive"))
      (node (ref "R306") (pin "1") (pinfunction "1_1") (pintype "passive"))
      (node (ref "U302") (pin "10") (pinfunction "+IN_10") (pintype "input"))
    )
    (net (code "80") (name "Net-(U302C--IN)") (class "Default")
      (node (ref "JP302") (pin "1") (pinfunction "1_1") (pintype "passive"))
      (node (ref "R302") (pin "2") (pinfunction "2_2") (pintype "passive"))
      (node (ref "R305") (pin "1") (pinfunction "1_1") (pintype "passive"))
      (node (ref "U302") (pin "9") (pinfunction "-IN_9") (pintype "input"))
    )
    (net (code "81") (name "Net-(U302C-OUT)") (class "Default")
      (node (ref "JP302") (pin "2") (pinfunction "2_2") (pintype "passive"))
      (node (ref "R305") (pin "2") (pinfunction "2_2") (pintype "passive"))
      (node (ref "R308") (pin "1") (pinfunction "1_1") (pintype "passive"))
      (node (ref "U302") (pin "8") (pinfunction "OUT_8") (pintype "output"))
    )
    (net (code "82") (name "Net-(U401-IN)") (class "Default")
      (node (ref "C403") (pin "1") (pinfunction "1_1") (pintype "passive"))
      (node (ref "R402") (pin "2") (pinfunction "2_2") (pintype "passive"))
      (node (ref "U401") (pin "1") (pinfunction "IN_1") (pintype "input"))
    )
    (net (code "83") (name "Net-(U402-IN)") (class "Default")
      (node (ref "C404") (pin "1") (pinfunction "1_1") (pintype "passive"))
      (node (ref "R403") (pin "2") (pinfunction "2_2") (pintype "passive"))
      (node (ref "U402") (pin "1") (pinfunction "IN_1") (pintype "input"))
    )
    (net (code "84") (name "V+") (class "Default")
      (node (ref "C305") (pin "1") (pinfunction "1_1") (pintype "passive"))
      (node (ref "C406") (pin "1") (pinfunction "1_1") (pintype "passive"))
      (node (ref "C409") (pin "+") (pinfunction "+_+") (pintype "passive"))
      (node (ref "J402") (pin "2") (pinfunction "2_2") (pintype "passive"))
      (node (ref "LED401") (pin "A") (pinfunction "A_A") (pintype "passive"))
      (node (ref "Q303") (pin "3") (pinfunction "C_3") (pintype "passive"))
      (node (ref "U302") (pin "4") (pinfunction "V+_4") (pintype "power_in"))
      (node (ref "U401") (pin "3") (pinfunction "OUT_3") (pintype "passive"))
    )
    (net (code "85") (name "V-") (class "Default")
      (node (ref "C104") (pin "2") (pinfunction "2_2") (pintype "passive"))
      (node (ref "C106") (pin "2") (pinfunction "2_2") (pintype "passive"))
      (node (ref "C108") (pin "2") (pinfunction "2_2") (pintype "passive"))
      (node (ref "C109") (pin "2") (pinfunction "2_2") (pintype "passive"))
      (node (ref "C110") (pin "2") (pinfunction "2_2") (pintype "passive"))
      (node (ref "C111") (pin "2") (pinfunction "2_2") (pintype "passive"))
      (node (ref "C114") (pin "2") (pinfunction "2_2") (pintype "passive"))
      (node (ref "C115") (pin "2") (pinfunction "2_2") (pintype "passive"))
      (node (ref "C201") (pin "2") (pinfunction "2_2") (pintype "passive"))
      (node (ref "C203") (pin "2") (pinfunction "2_2") (pintype "passive"))
      (node (ref "C205") (pin "2") (pinfunction "2_2") (pintype "passive"))
      (node (ref "C206") (pin "2") (pinfunction "2_2") (pintype "passive"))
      (node (ref "C207") (pin "2") (pinfunction "2_2") (pintype "passive"))
      (node (ref "C208") (pin "2") (pinfunction "2_2") (pintype "passive"))
      (node (ref "C211") (pin "2") (pinfunction "2_2") (pintype "passive"))
      (node (ref "C212") (pin "2") (pinfunction "2_2") (pintype "passive"))
      (node (ref "C301") (pin "2") (pinfunction "2_2") (pintype "passive"))
      (node (ref "C302") (pin "2") (pinfunction "2_2") (pintype "passive"))
      (node (ref "C303") (pin "2") (pinfunction "2_2") (pintype "passive"))
      (node (ref "C305") (pin "2") (pinfunction "2_2") (pintype "passive"))
      (node (ref "C306") (pin "2") (pinfunction "2_2") (pintype "passive"))
      (node (ref "C401") (pin "-") (pinfunction "-_-") (pintype "passive"))
      (node (ref "C402") (pin "2") (pinfunction "2_2") (pintype "passive"))
      (node (ref "C403") (pin "2") (pinfunction "2_2") (pintype "passive"))
      (node (ref "C404") (pin "2") (pinfunction "2_2") (pintype "passive"))
      (node (ref "C405") (pin "2") (pinfunction "2_2") (pintype "passive"))
      (node (ref "C406") (pin "2") (pinfunction "2_2") (pintype "passive"))
      (node (ref "C407") (pin "2") (pinfunction "2_2") (pintype "passive"))
      (node (ref "C408") (pin "2") (pinfunction "2_2") (pintype "passive"))
      (node (ref "C409") (pin "-") (pinfunction "-_-") (pintype "passive"))
      (node (ref "C410") (pin "-") (pinfunction "-_-") (pintype "passive"))
      (node (ref "C411") (pin "2") (pinfunction "2_2") (pintype "passive"))
      (node (ref "C412") (pin "2") (pinfunction "2_2") (pintype "passive"))
      (node (ref "C413") (pin "2") (pinfunction "2_2") (pintype "passive"))
      (node (ref "D401") (pin "A") (pinfunction "A1_A") (pintype "passive"))
      (node (ref "H401") (pin "B3,2") (pinfunction "MOUNT_B3,2") (pintype "passive"))
      (node (ref "H402") (pin "B3,2") (pinfunction "MOUNT_B3,2") (pintype "passive"))
      (node (ref "H403") (pin "B3,2") (pinfunction "MOUNT_B3,2") (pintype "passive"))
      (node (ref "H404") (pin "B3,2") (pinfunction "MOUNT_B3,2") (pintype "passive"))
      (node (ref "J101") (pin "G1") (pinfunction "GND1_G1") (pintype "power_in"))
      (node (ref "J101") (pin "G2") (pinfunction "GND1_G2") (pintype "power_in"))
      (node (ref "J101") (pin "G3") (pinfunction "GND1_G3") (pintype "power_in"))
      (node (ref "J101") (pin "G4") (pinfunction "GND1_G4") (pintype "power_in"))
      (node (ref "J102") (pin "G1") (pinfunction "GND1_G1") (pintype "power_in"))
      (node (ref "J102") (pin "G2") (pinfunction "GND1_G2") (pintype "power_in"))
      (node (ref "J102") (pin "G3") (pinfunction "GND1_G3") (pintype "power_in"))
      (node (ref "J102") (pin "G4") (pinfunction "GND1_G4") (pintype "power_in"))
      (node (ref "J302") (pin "G1") (pinfunction "GND1_G1") (pintype "power_in"))
      (node (ref "J302") (pin "G2") (pinfunction "GND1_G2") (pintype "power_in"))
      (node (ref "J302") (pin "G3") (pinfunction "GND1_G3") (pintype "power_in"))
      (node (ref "J302") (pin "G4") (pinfunction "GND1_G4") (pintype "power_in"))
      (node (ref "J401") (pin "2") (pinfunction "2_2") (pintype "passive"))
      (node (ref "J402") (pin "1") (pinfunction "1_1") (pintype "passive"))
      (node (ref "Q301") (pin "2") (pinfunction "S_2") (pintype "passive"))
      (node (ref "Q302") (pin "3") (pinfunction "C_3") (pintype "passive"))
      (node (ref "R101") (pin "2") (pinfunction "2_2") (pintype "passive"))
      (node (ref "R102") (pin "2") (pinfunction "2_2") (pintype "passive"))
      (node (ref "R103") (pin "2") (pinfunction "2_2") (pintype "passive"))
      (node (ref "R106") (pin "2") (pinfunction "2_2") (pintype "passive"))
      (node (ref "R107") (pin "2") (pinfunction "2_2") (pintype "passive"))
      (node (ref "R122") (pin "2") (pinfunction "2_2") (pintype "passive"))
      (node (ref "R123") (pin "2") (pinfunction "2_2") (pintype "passive"))
      (node (ref "R124") (pin "2") (pinfunction "2_2") (pintype "passive"))
      (node (ref "R125") (pin "2") (pinfunction "2_2") (pintype "passive"))
      (node (ref "R126") (pin "2") (pinfunction "2_2") (pintype "passive"))
      (node (ref "R127") (pin "2") (pinfunction "2_2") (pintype "passive"))
      (node (ref "R128") (pin "2") (pinfunction "2_2") (pintype "passive"))
      (node (ref "R129") (pin "2") (pinfunction "2_2") (pintype "passive"))
      (node (ref "R201") (pin "2") (pinfunction "2_2") (pintype "passive"))
      (node (ref "R202") (pin "2") (pinfunction "2_2") (pintype "passive"))
      (node (ref "R205") (pin "2") (pinfunction "2_2") (pintype "passive"))
      (node (ref "R206") (pin "2") (pinfunction "2_2") (pintype "passive"))
      (node (ref "R221") (pin "2") (pinfunction "2_2") (pintype "passive"))
      (node (ref "R222") (pin "2") (pinfunction "2_2") (pintype "passive"))
      (node (ref "R223") (pin "2") (pinfunction "2_2") (pintype "passive"))
      (node (ref "R224") (pin "2") (pinfunction "2_2") (pintype "passive"))
      (node (ref "R225") (pin "2") (pinfunction "2_2") (pintype "passive"))
      (node (ref "R226") (pin "2") (pinfunction "2_2") (pintype "passive"))
      (node (ref "R227") (pin "2") (pinfunction "2_2") (pintype "passive"))
      (node (ref "R228") (pin "2") (pinfunction "2_2") (pintype "passive"))
      (node (ref "R301") (pin "1") (pinfunction "A_1") (pintype "passive"))
      (node (ref "R307") (pin "2") (pinfunction "2_2") (pintype "passive"))
      (node (ref "R311") (pin "2") (pinfunction "2_2") (pintype "passive"))
      (node (ref "R312") (pin "1") (pinfunction "1_1") (pintype "passive"))
      (node (ref "R406") (pin "2") (pinfunction "2_2") (pintype "passive"))
      (node (ref "R407") (pin "2") (pinfunction "2_2") (pintype "passive"))
      (node (ref "T101") (pin "10") (pinfunction "F3_10") (pintype "passive"))
      (node (ref "T102") (pin "9") (pinfunction "F4_9") (pintype "passive"))
      (node (ref "TP1") (pin "GND") (pinfunction "GND1_GND") (pintype "power_in"))
      (node (ref "TP10") (pin "GND") (pinfunction "GND1_GND") (pintype "power_in"))
      (node (ref "TP11") (pin "GND") (pinfunction "GND1_GND") (pintype "power_in"))
      (node (ref "TP12") (pin "GND") (pinfunction "GND1_GND") (pintype "power_in"))
      (node (ref "TP13") (pin "GND") (pinfunction "GND1_GND") (pintype "power_in"))
      (node (ref "TP14") (pin "GND") (pinfunction "GND1_GND") (pintype "power_in"))
      (node (ref "TP15") (pin "GND") (pinfunction "GND1_GND") (pintype "power_in"))
      (node (ref "TP16") (pin "GND") (pinfunction "GND1_GND") (pintype "power_in"))
      (node (ref "TP17") (pin "GND") (pinfunction "GND1_GND") (pintype "power_in"))
      (node (ref "TP18") (pin "GND") (pinfunction "GND1_GND") (pintype "power_in"))
      (node (ref "TP19") (pin "GND") (pinfunction "GND1_GND") (pintype "power_in"))
      (node (ref "TP2") (pin "GND") (pinfunction "GND1_GND") (pintype "power_in"))
      (node (ref "TP3") (pin "GND") (pinfunction "GND1_GND") (pintype "power_in"))
      (node (ref "TP4") (pin "GND") (pinfunction "GND1_GND") (pintype "power_in"))
      (node (ref "TP5") (pin "GND") (pinfunction "GND1_GND") (pintype "power_in"))
      (node (ref "TP6") (pin "GND") (pinfunction "GND1_GND") (pintype "power_in"))
      (node (ref "TP7") (pin "GND") (pinfunction "GND1_GND") (pintype "power_in"))
      (node (ref "TP8") (pin "GND") (pinfunction "GND1_GND") (pintype "power_in"))
      (node (ref "TP9") (pin "GND") (pinfunction "GND1_GND") (pintype "power_in"))
      (node (ref "U301") (pin "3") (pinfunction "GND_3") (pintype "power_in"))
      (node (ref "U302") (pin "11") (pinfunction "V-_11") (pintype "power_in"))
      (node (ref "U401") (pin "2") (pinfunction "GND_2") (pintype "input"))
      (node (ref "U402") (pin "2") (pinfunction "GND_2") (pintype "input"))
      (node (ref "X402") (pin "P1") (pinfunction "P$1_P1") (pintype "bidirectional"))
      (node (ref "X402") (pin "P2") (pinfunction "P$2_P2") (pintype "bidirectional"))
    )
    (net (code "86") (name "VB") (class "Default")
      (node (ref "C116") (pin "1") (pinfunction "1_1") (pintype "passive"))
      (node (ref "C117") (pin "1") (pinfunction "1_1") (pintype "passive"))
      (node (ref "C408") (pin "1") (pinfunction "1_1") (pintype "passive"))
      (node (ref "C411") (pin "1") (pinfunction "1_1") (pintype "passive"))
      (node (ref "C412") (pin "1") (pinfunction "1_1") (pintype "passive"))
      (node (ref "C413") (pin "1") (pinfunction "1_1") (pintype "passive"))
      (node (ref "L103") (pin "2") (pinfunction "2_2") (pintype "passive"))
      (node (ref "L104") (pin "2") (pinfunction "2_2") (pintype "passive"))
      (node (ref "L402") (pin "2") (pinfunction "2_2") (pintype "passive"))
      (node (ref "R132") (pin "1") (pinfunction "1_1") (pintype "passive"))
      (node (ref "R404") (pin "2") (pinfunction "2_2") (pintype "passive"))
      (node (ref "R405") (pin "2") (pinfunction "2_2") (pintype "passive"))
    )
    (net (code "87") (name "unconnected-(J402-Pad4)") (class "Default")
      (node (ref "J402") (pin "4") (pinfunction "4_4") (pintype "passive"))
    )
  )
)
